# FullTouchSmartphone.net
KiCad netlist of a schematic drawn in EAGLE
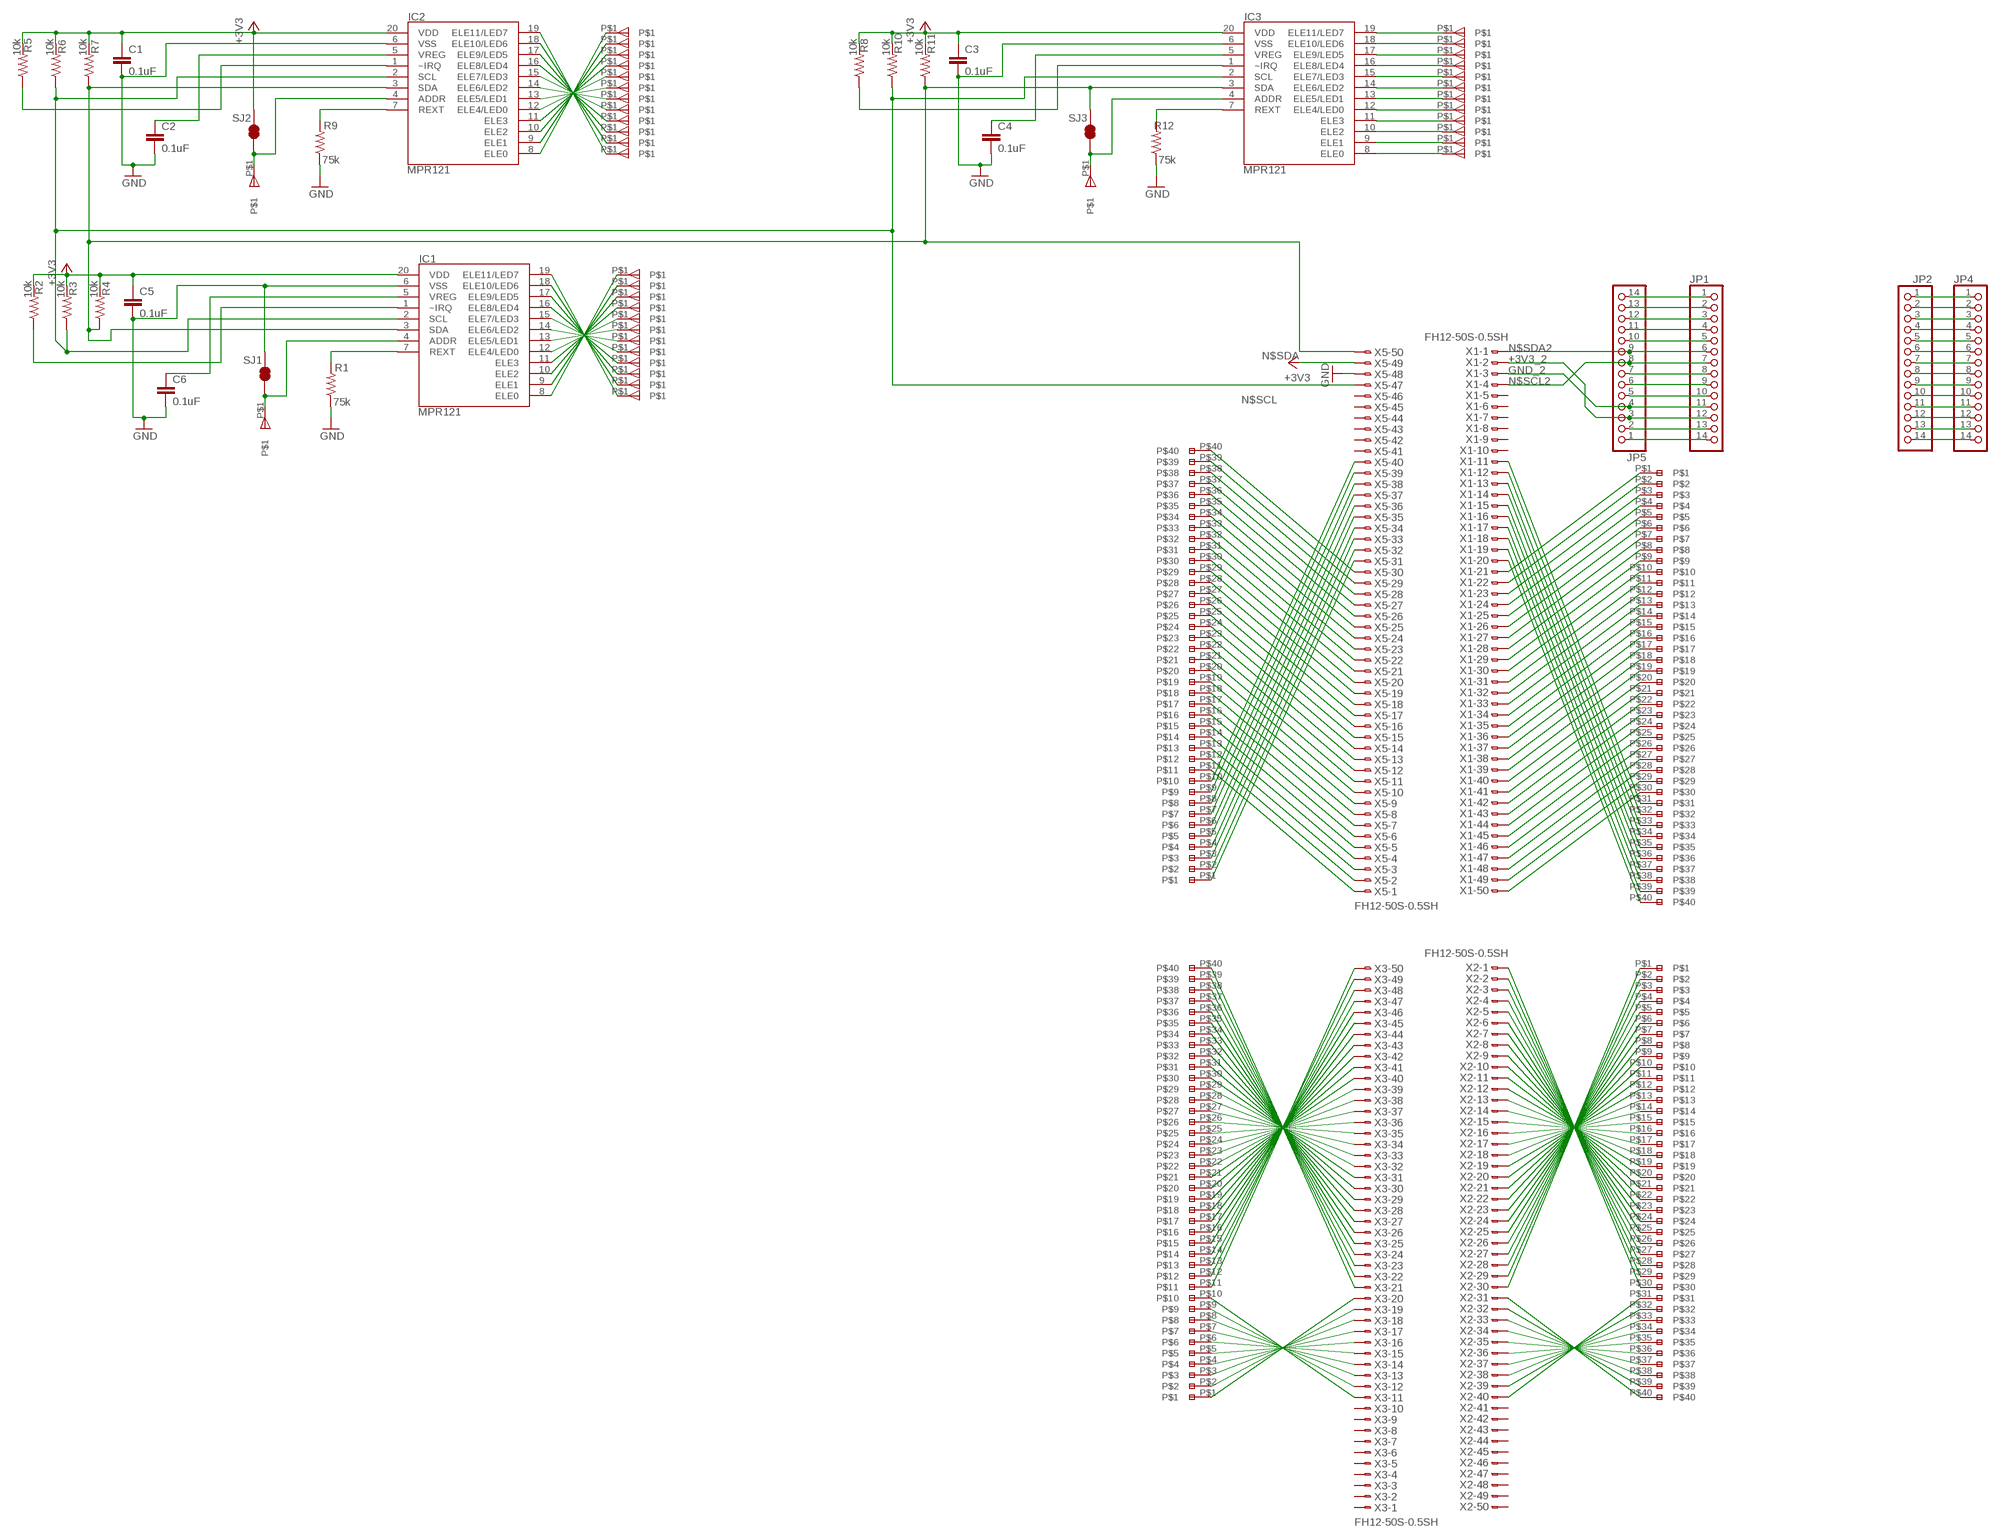
[diagram p0: schematic, sheet 1]

(export (version "E")
  (design (tool "Eeschema 10.0.6"))
  (components
    (comp (ref "C1")
      (value "0.1uF")
      (footprint "eagle-import:0603-CAP")
      (libsource (lib "eagle-import") (part "CAP0603-CAP"))
    )
    (comp (ref "C2")
      (value "0.1uF")
      (footprint "eagle-import:0603-CAP")
      (libsource (lib "eagle-import") (part "CAP0603-CAP"))
    )
    (comp (ref "C3")
      (value "0.1uF")
      (footprint "eagle-import:0603-CAP")
      (libsource (lib "eagle-import") (part "CAP0603-CAP"))
    )
    (comp (ref "C4")
      (value "0.1uF")
      (footprint "eagle-import:0603-CAP")
      (libsource (lib "eagle-import") (part "CAP0603-CAP"))
    )
    (comp (ref "C5")
      (value "0.1uF")
      (footprint "eagle-import:0603-CAP")
      (libsource (lib "eagle-import") (part "CAP0603-CAP"))
    )
    (comp (ref "C6")
      (value "0.1uF")
      (footprint "eagle-import:0603-CAP")
      (libsource (lib "eagle-import") (part "CAP0603-CAP"))
    )
    (comp (ref "IC1")
      (value "MPR121")
      (footprint "eagle-import:QFN-20-0.4MM-V2")
      (libsource (lib "eagle-import") (part "MPR121V2"))
    )
    (comp (ref "IC2")
      (value "MPR121")
      (footprint "eagle-import:QFN-20-0.4MM-V2")
      (libsource (lib "eagle-import") (part "MPR121V2"))
    )
    (comp (ref "IC3")
      (value "MPR121")
      (footprint "eagle-import:QFN-20-0.4MM-V2")
      (libsource (lib "eagle-import") (part "MPR121V2"))
    )
    (comp (ref "JP1")
      (value "PINHD-1X14")
      (footprint "eagle-import:1X14")
      (libsource (lib "eagle-import") (part "PINHD-1X14"))
    )
    (comp (ref "JP2")
      (value "PINHD-1X14")
      (footprint "eagle-import:1X14")
      (libsource (lib "eagle-import") (part "PINHD-1X14"))
    )
    (comp (ref "JP4")
      (value "PINHD-1X14")
      (footprint "eagle-import:1X14")
      (libsource (lib "eagle-import") (part "PINHD-1X14"))
    )
    (comp (ref "JP5")
      (value "PINHD-1X14")
      (footprint "eagle-import:1X14")
      (libsource (lib "eagle-import") (part "PINHD-1X14"))
    )
    (comp (ref "R1")
      (value "75k")
      (footprint "eagle-import:0603-RES")
      (libsource (lib "eagle-import") (part "RESISTOR0603-RES"))
    )
    (comp (ref "R2")
      (value "10k")
      (footprint "eagle-import:0603-RES")
      (libsource (lib "eagle-import") (part "RESISTOR0603-RES"))
    )
    (comp (ref "R3")
      (value "10k")
      (footprint "eagle-import:0603-RES")
      (libsource (lib "eagle-import") (part "RESISTOR0603-RES"))
    )
    (comp (ref "R4")
      (value "10k")
      (footprint "eagle-import:0603-RES")
      (libsource (lib "eagle-import") (part "RESISTOR0603-RES"))
    )
    (comp (ref "R5")
      (value "10k")
      (footprint "eagle-import:0603-RES")
      (libsource (lib "eagle-import") (part "RESISTOR0603-RES"))
    )
    (comp (ref "R6")
      (value "10k")
      (footprint "eagle-import:0603-RES")
      (libsource (lib "eagle-import") (part "RESISTOR0603-RES"))
    )
    (comp (ref "R7")
      (value "10k")
      (footprint "eagle-import:0603-RES")
      (libsource (lib "eagle-import") (part "RESISTOR0603-RES"))
    )
    (comp (ref "R8")
      (value "10k")
      (footprint "eagle-import:0603-RES")
      (libsource (lib "eagle-import") (part "RESISTOR0603-RES"))
    )
    (comp (ref "R9")
      (value "75k")
      (footprint "eagle-import:0603-RES")
      (libsource (lib "eagle-import") (part "RESISTOR0603-RES"))
    )
    (comp (ref "R10")
      (value "10k")
      (footprint "eagle-import:0603-RES")
      (libsource (lib "eagle-import") (part "RESISTOR0603-RES"))
    )
    (comp (ref "R11")
      (value "10k")
      (footprint "eagle-import:0603-RES")
      (libsource (lib "eagle-import") (part "RESISTOR0603-RES"))
    )
    (comp (ref "R12")
      (value "75k")
      (footprint "eagle-import:0603-RES")
      (libsource (lib "eagle-import") (part "RESISTOR0603-RES"))
    )
    (comp (ref "SJ1")
      (value "SOLDERJUMPERTRACE")
      (footprint "eagle-import:SJ_2S-TRACE")
      (libsource (lib "eagle-import") (part "SOLDERJUMPERTRACE"))
    )
    (comp (ref "SJ2")
      (value "SOLDERJUMPERTRACE")
      (footprint "eagle-import:SJ_2S-TRACE")
      (libsource (lib "eagle-import") (part "SOLDERJUMPERTRACE"))
    )
    (comp (ref "SJ3")
      (value "SOLDERJUMPERTRACE")
      (footprint "eagle-import:SJ_2S-TRACE")
      (libsource (lib "eagle-import") (part "SOLDERJUMPERTRACE"))
    )
    (comp (ref "U$1")
      (value "AXE640124")
      (footprint "eagle-import:AXE640124")
      (libsource (lib "eagle-import") (part "AXE640124"))
    )
    (comp (ref "U$2")
      (value "AXE640124")
      (footprint "eagle-import:AXE640124")
      (libsource (lib "eagle-import") (part "AXE640124"))
    )
    (comp (ref "U$3")
      (value "AXE540127")
      (footprint "eagle-import:AXE540127")
      (libsource (lib "eagle-import") (part "AXE540127"))
    )
    (comp (ref "U$4")
      (value "SINGLE_LÖT_SPOT_K")
      (footprint "eagle-import:SINGLE_LÖT_SPOT_K")
      (libsource (lib "eagle-import") (part "SINGLE_LÖT_SPOT_K"))
    )
    (comp (ref "U$5")
      (value "SINGLE_LÖT_SPOT_K")
      (footprint "eagle-import:SINGLE_LÖT_SPOT_K")
      (libsource (lib "eagle-import") (part "SINGLE_LÖT_SPOT_K"))
    )
    (comp (ref "U$6")
      (value "SINGLE_LÖT_SPOT_K")
      (footprint "eagle-import:SINGLE_LÖT_SPOT_K")
      (libsource (lib "eagle-import") (part "SINGLE_LÖT_SPOT_K"))
    )
    (comp (ref "U$7")
      (value "SINGLE_LÖT_SPOT_K")
      (footprint "eagle-import:SINGLE_LÖT_SPOT_K")
      (libsource (lib "eagle-import") (part "SINGLE_LÖT_SPOT_K"))
    )
    (comp (ref "U$8")
      (value "SINGLE_LÖT_SPOT_K")
      (footprint "eagle-import:SINGLE_LÖT_SPOT_K")
      (libsource (lib "eagle-import") (part "SINGLE_LÖT_SPOT_K"))
    )
    (comp (ref "U$9")
      (value "SINGLE_LÖT_SPOT_K")
      (footprint "eagle-import:SINGLE_LÖT_SPOT_K")
      (libsource (lib "eagle-import") (part "SINGLE_LÖT_SPOT_K"))
    )
    (comp (ref "U$10")
      (value "SINGLE_LÖT_SPOT_K")
      (footprint "eagle-import:SINGLE_LÖT_SPOT_K")
      (libsource (lib "eagle-import") (part "SINGLE_LÖT_SPOT_K"))
    )
    (comp (ref "U$11")
      (value "SINGLE_LÖT_SPOT_K")
      (footprint "eagle-import:SINGLE_LÖT_SPOT_K")
      (libsource (lib "eagle-import") (part "SINGLE_LÖT_SPOT_K"))
    )
    (comp (ref "U$12")
      (value "SINGLE_LÖT_SPOT_K")
      (footprint "eagle-import:SINGLE_LÖT_SPOT_K")
      (libsource (lib "eagle-import") (part "SINGLE_LÖT_SPOT_K"))
    )
    (comp (ref "U$13")
      (value "SINGLE_LÖT_SPOT_K")
      (footprint "eagle-import:SINGLE_LÖT_SPOT_K")
      (libsource (lib "eagle-import") (part "SINGLE_LÖT_SPOT_K"))
    )
    (comp (ref "U$14")
      (value "SINGLE_LÖT_SPOT_K")
      (footprint "eagle-import:SINGLE_LÖT_SPOT_K")
      (libsource (lib "eagle-import") (part "SINGLE_LÖT_SPOT_K"))
    )
    (comp (ref "U$15")
      (value "SINGLE_LÖT_SPOT_K")
      (footprint "eagle-import:SINGLE_LÖT_SPOT_K")
      (libsource (lib "eagle-import") (part "SINGLE_LÖT_SPOT_K"))
    )
    (comp (ref "U$25")
      (value "SINGLE_LÖT_SPOT_K")
      (footprint "eagle-import:SINGLE_LÖT_SPOT_K")
      (libsource (lib "eagle-import") (part "SINGLE_LÖT_SPOT_K"))
    )
    (comp (ref "U$26")
      (value "SINGLE_LÖT_SPOT_K")
      (footprint "eagle-import:SINGLE_LÖT_SPOT_K")
      (libsource (lib "eagle-import") (part "SINGLE_LÖT_SPOT_K"))
    )
    (comp (ref "U$27")
      (value "SINGLE_LÖT_SPOT_K")
      (footprint "eagle-import:SINGLE_LÖT_SPOT_K")
      (libsource (lib "eagle-import") (part "SINGLE_LÖT_SPOT_K"))
    )
    (comp (ref "U$28")
      (value "SINGLE_LÖT_SPOT_K")
      (footprint "eagle-import:SINGLE_LÖT_SPOT_K")
      (libsource (lib "eagle-import") (part "SINGLE_LÖT_SPOT_K"))
    )
    (comp (ref "U$29")
      (value "SINGLE_LÖT_SPOT_K")
      (footprint "eagle-import:SINGLE_LÖT_SPOT_K")
      (libsource (lib "eagle-import") (part "SINGLE_LÖT_SPOT_K"))
    )
    (comp (ref "U$30")
      (value "SINGLE_LÖT_SPOT_K")
      (footprint "eagle-import:SINGLE_LÖT_SPOT_K")
      (libsource (lib "eagle-import") (part "SINGLE_LÖT_SPOT_K"))
    )
    (comp (ref "U$31")
      (value "SINGLE_LÖT_SPOT_K")
      (footprint "eagle-import:SINGLE_LÖT_SPOT_K")
      (libsource (lib "eagle-import") (part "SINGLE_LÖT_SPOT_K"))
    )
    (comp (ref "U$32")
      (value "SINGLE_LÖT_SPOT_K")
      (footprint "eagle-import:SINGLE_LÖT_SPOT_K")
      (libsource (lib "eagle-import") (part "SINGLE_LÖT_SPOT_K"))
    )
    (comp (ref "U$33")
      (value "SINGLE_LÖT_SPOT_K")
      (footprint "eagle-import:SINGLE_LÖT_SPOT_K")
      (libsource (lib "eagle-import") (part "SINGLE_LÖT_SPOT_K"))
    )
    (comp (ref "U$34")
      (value "SINGLE_LÖT_SPOT_K")
      (footprint "eagle-import:SINGLE_LÖT_SPOT_K")
      (libsource (lib "eagle-import") (part "SINGLE_LÖT_SPOT_K"))
    )
    (comp (ref "U$35")
      (value "SINGLE_LÖT_SPOT_K")
      (footprint "eagle-import:SINGLE_LÖT_SPOT_K")
      (libsource (lib "eagle-import") (part "SINGLE_LÖT_SPOT_K"))
    )
    (comp (ref "U$36")
      (value "SINGLE_LÖT_SPOT_K")
      (footprint "eagle-import:SINGLE_LÖT_SPOT_K")
      (libsource (lib "eagle-import") (part "SINGLE_LÖT_SPOT_K"))
    )
    (comp (ref "U$37")
      (value "SINGLE_LÖT_SPOT_K")
      (footprint "eagle-import:SINGLE_LÖT_SPOT_K")
      (libsource (lib "eagle-import") (part "SINGLE_LÖT_SPOT_K"))
    )
    (comp (ref "U$38")
      (value "SINGLE_LÖT_SPOT_K")
      (footprint "eagle-import:SINGLE_LÖT_SPOT_K")
      (libsource (lib "eagle-import") (part "SINGLE_LÖT_SPOT_K"))
    )
    (comp (ref "U$39")
      (value "SINGLE_LÖT_SPOT_K")
      (footprint "eagle-import:SINGLE_LÖT_SPOT_K")
      (libsource (lib "eagle-import") (part "SINGLE_LÖT_SPOT_K"))
    )
    (comp (ref "U$40")
      (value "SINGLE_LÖT_SPOT_K")
      (footprint "eagle-import:SINGLE_LÖT_SPOT_K")
      (libsource (lib "eagle-import") (part "SINGLE_LÖT_SPOT_K"))
    )
    (comp (ref "U$40PIN-BACK")
      (value "AXE540127")
      (footprint "eagle-import:AXE540127")
      (libsource (lib "eagle-import") (part "AXE540127"))
    )
    (comp (ref "U$41")
      (value "SINGLE_LÖT_SPOT_K")
      (footprint "eagle-import:SINGLE_LÖT_SPOT_K")
      (libsource (lib "eagle-import") (part "SINGLE_LÖT_SPOT_K"))
    )
    (comp (ref "U$42")
      (value "SINGLE_LÖT_SPOT_K")
      (footprint "eagle-import:SINGLE_LÖT_SPOT_K")
      (libsource (lib "eagle-import") (part "SINGLE_LÖT_SPOT_K"))
    )
    (comp (ref "U$43")
      (value "SINGLE_LÖT_SPOT_K")
      (footprint "eagle-import:SINGLE_LÖT_SPOT_K")
      (libsource (lib "eagle-import") (part "SINGLE_LÖT_SPOT_K"))
    )
    (comp (ref "U$44")
      (value "SINGLE_LÖT_SPOT_K")
      (footprint "eagle-import:SINGLE_LÖT_SPOT_K")
      (libsource (lib "eagle-import") (part "SINGLE_LÖT_SPOT_K"))
    )
    (comp (ref "U$45")
      (value "SINGLE_LÖT_SPOT_K")
      (footprint "eagle-import:SINGLE_LÖT_SPOT_K")
      (libsource (lib "eagle-import") (part "SINGLE_LÖT_SPOT_K"))
    )
    (comp (ref "U$46")
      (value "SINGLE_LÖT_SPOT_K")
      (footprint "eagle-import:SINGLE_LÖT_SPOT_K")
      (libsource (lib "eagle-import") (part "SINGLE_LÖT_SPOT_K"))
    )
    (comp (ref "U$47")
      (value "SINGLE_LÖT_SPOT_K")
      (footprint "eagle-import:SINGLE_LÖT_SPOT_K")
      (libsource (lib "eagle-import") (part "SINGLE_LÖT_SPOT_K"))
    )
    (comp (ref "U$48")
      (value "SINGLE_LÖT_SPOT_K")
      (footprint "eagle-import:SINGLE_LÖT_SPOT_K")
      (libsource (lib "eagle-import") (part "SINGLE_LÖT_SPOT_K"))
    )
    (comp (ref "U$49")
      (value "SINGLE_LÖT_SPOT_K")
      (footprint "eagle-import:SINGLE_LÖT_SPOT_K")
      (libsource (lib "eagle-import") (part "SINGLE_LÖT_SPOT_K"))
    )
    (comp (ref "U$50")
      (value "SINGLE_LÖT_SPOT_K")
      (footprint "eagle-import:SINGLE_LÖT_SPOT_K")
      (libsource (lib "eagle-import") (part "SINGLE_LÖT_SPOT_K"))
    )
    (comp (ref "U$51")
      (value "SINGLE_LÖT_SPOT_K")
      (footprint "eagle-import:SINGLE_LÖT_SPOT_K")
      (libsource (lib "eagle-import") (part "SINGLE_LÖT_SPOT_K"))
    )
    (comp (ref "X1")
      (value "FH12-50S-0.5SH")
      (footprint "eagle-import:FH12-50S-0.5SH")
      (fields (field (name "MPN") "FH12-50S-0.5SH(55)"))
      (libsource (lib "eagle-import") (part "FH12-50S-0.5SH"))
    )
    (comp (ref "X2")
      (value "FH12-50S-0.5SH")
      (footprint "eagle-import:FH12-50S-0.5SH")
      (fields (field (name "MPN") "FH12-50S-0.5SH(55)"))
      (libsource (lib "eagle-import") (part "FH12-50S-0.5SH"))
    )
    (comp (ref "X3")
      (value "FH12-50S-0.5SH")
      (footprint "eagle-import:FH12-50S-0.5SH")
      (fields (field (name "MPN") "FH12-50S-0.5SH(55)"))
      (libsource (lib "eagle-import") (part "FH12-50S-0.5SH"))
    )
    (comp (ref "X5")
      (value "FH12-50S-0.5SH")
      (footprint "eagle-import:FH12-50S-0.5SH")
      (fields (field (name "MPN") "FH12-50S-0.5SH(55)"))
      (libsource (lib "eagle-import") (part "FH12-50S-0.5SH"))
    )
  )
  (nets
    (net (code "1") (name "+3V3") (class "Default")
      (node (ref "C1") (pin "1") (pinfunction "1_1") (pintype "passive"))
      (node (ref "C3") (pin "1") (pinfunction "1_1") (pintype "passive"))
      (node (ref "C5") (pin "1") (pinfunction "1_1") (pintype "passive"))
      (node (ref "IC1") (pin "20") (pinfunction "VDD_20") (pintype "bidirectional"))
      (node (ref "IC2") (pin "20") (pinfunction "VDD_20") (pintype "bidirectional"))
      (node (ref "IC3") (pin "20") (pinfunction "VDD_20") (pintype "bidirectional"))
      (node (ref "R10") (pin "2") (pinfunction "2_2") (pintype "passive"))
      (node (ref "R11") (pin "2") (pinfunction "2_2") (pintype "passive"))
      (node (ref "R2") (pin "2") (pinfunction "2_2") (pintype "passive"))
      (node (ref "R3") (pin "2") (pinfunction "2_2") (pintype "passive"))
      (node (ref "R4") (pin "2") (pinfunction "2_2") (pintype "passive"))
      (node (ref "R5") (pin "2") (pinfunction "2_2") (pintype "passive"))
      (node (ref "R6") (pin "2") (pinfunction "2_2") (pintype "passive"))
      (node (ref "R7") (pin "2") (pinfunction "2_2") (pintype "passive"))
      (node (ref "R8") (pin "2") (pinfunction "2_2") (pintype "passive"))
      (node (ref "SJ2") (pin "2") (pinfunction "2_2") (pintype "passive"))
      (node (ref "X5") (pin "49") (pinfunction "1_49") (pintype "passive"))
    )
    (net (code "2") (name "/+3V3_2") (class "Default")
      (node (ref "JP1") (pin "12") (pinfunction "12_12") (pintype "passive"))
      (node (ref "JP5") (pin "3") (pinfunction "3_3") (pintype "passive"))
      (node (ref "X1") (pin "2") (pinfunction "1_2") (pintype "passive"))
    )
    (net (code "3") (name "/GND_2") (class "Default")
      (node (ref "JP1") (pin "11") (pinfunction "11_11") (pintype "passive"))
      (node (ref "JP5") (pin "4") (pinfunction "4_4") (pintype "passive"))
      (node (ref "X1") (pin "3") (pinfunction "1_3") (pintype "passive"))
    )
    (net (code "4") (name "/N$SCL") (class "Default")
      (node (ref "IC1") (pin "2") (pinfunction "SCL_2") (pintype "bidirectional"))
      (node (ref "IC2") (pin "2") (pinfunction "SCL_2") (pintype "bidirectional"))
      (node (ref "IC3") (pin "2") (pinfunction "SCL_2") (pintype "bidirectional"))
      (node (ref "R10") (pin "1") (pinfunction "1_1") (pintype "passive"))
      (node (ref "R3") (pin "1") (pinfunction "1_1") (pintype "passive"))
      (node (ref "R6") (pin "1") (pinfunction "1_1") (pintype "passive"))
      (node (ref "X5") (pin "47") (pinfunction "1_47") (pintype "passive"))
    )
    (net (code "5") (name "/N$SCL2") (class "Default")
      (node (ref "JP1") (pin "7") (pinfunction "7_7") (pintype "passive"))
      (node (ref "JP5") (pin "8") (pinfunction "8_8") (pintype "passive"))
      (node (ref "X1") (pin "4") (pinfunction "1_4") (pintype "passive"))
    )
    (net (code "6") (name "/N$SDA") (class "Default")
      (node (ref "IC1") (pin "3") (pinfunction "SDA_3") (pintype "bidirectional"))
      (node (ref "IC2") (pin "3") (pinfunction "SDA_3") (pintype "bidirectional"))
      (node (ref "IC3") (pin "3") (pinfunction "SDA_3") (pintype "bidirectional"))
      (node (ref "R11") (pin "1") (pinfunction "1_1") (pintype "passive"))
      (node (ref "R4") (pin "1") (pinfunction "1_1") (pintype "passive"))
      (node (ref "R7") (pin "1") (pinfunction "1_1") (pintype "passive"))
      (node (ref "SJ3") (pin "2") (pinfunction "2_2") (pintype "passive"))
      (node (ref "X5") (pin "50") (pinfunction "1_50") (pintype "passive"))
    )
    (net (code "7") (name "/N$SDA2") (class "Default")
      (node (ref "JP1") (pin "6") (pinfunction "6_6") (pintype "passive"))
      (node (ref "JP5") (pin "9") (pinfunction "9_9") (pintype "passive"))
      (node (ref "X1") (pin "1") (pinfunction "1_1") (pintype "passive"))
    )
    (net (code "8") (name "GND") (class "Default")
      (node (ref "C1") (pin "2") (pinfunction "2_2") (pintype "passive"))
      (node (ref "C2") (pin "2") (pinfunction "2_2") (pintype "passive"))
      (node (ref "C3") (pin "2") (pinfunction "2_2") (pintype "passive"))
      (node (ref "C4") (pin "2") (pinfunction "2_2") (pintype "passive"))
      (node (ref "C5") (pin "2") (pinfunction "2_2") (pintype "passive"))
      (node (ref "C6") (pin "2") (pinfunction "2_2") (pintype "passive"))
      (node (ref "IC1") (pin "6") (pinfunction "VSS_6") (pintype "bidirectional"))
      (node (ref "IC2") (pin "6") (pinfunction "VSS_6") (pintype "bidirectional"))
      (node (ref "IC3") (pin "6") (pinfunction "VSS_6") (pintype "bidirectional"))
      (node (ref "R1") (pin "1") (pinfunction "1_1") (pintype "passive"))
      (node (ref "R12") (pin "1") (pinfunction "1_1") (pintype "passive"))
      (node (ref "R9") (pin "1") (pinfunction "1_1") (pintype "passive"))
      (node (ref "SJ1") (pin "2") (pinfunction "2_2") (pintype "passive"))
      (node (ref "X5") (pin "48") (pinfunction "1_48") (pintype "passive"))
    )
    (net (code "9") (name "Net-(IC1-ADDR)") (class "Default")
      (node (ref "IC1") (pin "4") (pinfunction "ADDR_4") (pintype "bidirectional"))
      (node (ref "SJ1") (pin "1") (pinfunction "1_1") (pintype "passive"))
      (node (ref "U$37") (pin "P$1") (pinfunction "P$1_P$1") (pintype "passive"))
    )
    (net (code "10") (name "Net-(IC1-ELE0)") (class "Default")
      (node (ref "IC1") (pin "8") (pinfunction "ELE0_8") (pintype "bidirectional"))
      (node (ref "U$4") (pin "P$1") (pinfunction "P$1_P$1") (pintype "passive"))
    )
    (net (code "11") (name "Net-(IC1-ELE1)") (class "Default")
      (node (ref "IC1") (pin "9") (pinfunction "ELE1_9") (pintype "bidirectional"))
      (node (ref "U$5") (pin "P$1") (pinfunction "P$1_P$1") (pintype "passive"))
    )
    (net (code "12") (name "Net-(IC1-ELE2)") (class "Default")
      (node (ref "IC1") (pin "10") (pinfunction "ELE2_10") (pintype "bidirectional"))
      (node (ref "U$6") (pin "P$1") (pinfunction "P$1_P$1") (pintype "passive"))
    )
    (net (code "13") (name "Net-(IC1-ELE3)") (class "Default")
      (node (ref "IC1") (pin "11") (pinfunction "ELE3_11") (pintype "bidirectional"))
      (node (ref "U$7") (pin "P$1") (pinfunction "P$1_P$1") (pintype "passive"))
    )
    (net (code "14") (name "Net-(IC1-ELE4{slash}LED0)") (class "Default")
      (node (ref "IC1") (pin "12") (pinfunction "ELE4/LED0_12") (pintype "bidirectional"))
      (node (ref "U$8") (pin "P$1") (pinfunction "P$1_P$1") (pintype "passive"))
    )
    (net (code "15") (name "Net-(IC1-ELE5{slash}LED1)") (class "Default")
      (node (ref "IC1") (pin "13") (pinfunction "ELE5/LED1_13") (pintype "bidirectional"))
      (node (ref "U$9") (pin "P$1") (pinfunction "P$1_P$1") (pintype "passive"))
    )
    (net (code "16") (name "Net-(IC1-ELE6{slash}LED2)") (class "Default")
      (node (ref "IC1") (pin "14") (pinfunction "ELE6/LED2_14") (pintype "bidirectional"))
      (node (ref "U$10") (pin "P$1") (pinfunction "P$1_P$1") (pintype "passive"))
    )
    (net (code "17") (name "Net-(IC1-ELE7{slash}LED3)") (class "Default")
      (node (ref "IC1") (pin "15") (pinfunction "ELE7/LED3_15") (pintype "bidirectional"))
      (node (ref "U$11") (pin "P$1") (pinfunction "P$1_P$1") (pintype "passive"))
    )
    (net (code "18") (name "Net-(IC1-ELE8{slash}LED4)") (class "Default")
      (node (ref "IC1") (pin "16") (pinfunction "ELE8/LED4_16") (pintype "bidirectional"))
      (node (ref "U$12") (pin "P$1") (pinfunction "P$1_P$1") (pintype "passive"))
    )
    (net (code "19") (name "Net-(IC1-ELE9{slash}LED5)") (class "Default")
      (node (ref "IC1") (pin "17") (pinfunction "ELE9/LED5_17") (pintype "bidirectional"))
      (node (ref "U$13") (pin "P$1") (pinfunction "P$1_P$1") (pintype "passive"))
    )
    (net (code "20") (name "Net-(IC1-ELE10{slash}LED6)") (class "Default")
      (node (ref "IC1") (pin "18") (pinfunction "ELE10/LED6_18") (pintype "bidirectional"))
      (node (ref "U$14") (pin "P$1") (pinfunction "P$1_P$1") (pintype "passive"))
    )
    (net (code "21") (name "Net-(IC1-ELE11{slash}LED7)") (class "Default")
      (node (ref "IC1") (pin "19") (pinfunction "ELE11/LED7_19") (pintype "bidirectional"))
      (node (ref "U$15") (pin "P$1") (pinfunction "P$1_P$1") (pintype "passive"))
    )
    (net (code "22") (name "Net-(IC1-REXT)") (class "Default")
      (node (ref "IC1") (pin "7") (pinfunction "REXT_7") (pintype "bidirectional"))
      (node (ref "R1") (pin "2") (pinfunction "2_2") (pintype "passive"))
    )
    (net (code "23") (name "Net-(IC1-VREG)") (class "Default")
      (node (ref "C6") (pin "1") (pinfunction "1_1") (pintype "passive"))
      (node (ref "IC1") (pin "5") (pinfunction "VREG_5") (pintype "bidirectional"))
    )
    (net (code "24") (name "Net-(IC1-~{IRQ})") (class "Default")
      (node (ref "IC1") (pin "1") (pinfunction "~{IRQ}_1") (pintype "bidirectional"))
      (node (ref "R2") (pin "1") (pinfunction "1_1") (pintype "passive"))
    )
    (net (code "25") (name "Net-(IC2-ADDR)") (class "Default")
      (node (ref "IC2") (pin "4") (pinfunction "ADDR_4") (pintype "bidirectional"))
      (node (ref "SJ2") (pin "1") (pinfunction "1_1") (pintype "passive"))
      (node (ref "U$38") (pin "P$1") (pinfunction "P$1_P$1") (pintype "passive"))
    )
    (net (code "26") (name "Net-(IC2-ELE0)") (class "Default")
      (node (ref "IC2") (pin "8") (pinfunction "ELE0_8") (pintype "bidirectional"))
      (node (ref "U$36") (pin "P$1") (pinfunction "P$1_P$1") (pintype "passive"))
    )
    (net (code "27") (name "Net-(IC2-ELE1)") (class "Default")
      (node (ref "IC2") (pin "9") (pinfunction "ELE1_9") (pintype "bidirectional"))
      (node (ref "U$35") (pin "P$1") (pinfunction "P$1_P$1") (pintype "passive"))
    )
    (net (code "28") (name "Net-(IC2-ELE2)") (class "Default")
      (node (ref "IC2") (pin "10") (pinfunction "ELE2_10") (pintype "bidirectional"))
      (node (ref "U$34") (pin "P$1") (pinfunction "P$1_P$1") (pintype "passive"))
    )
    (net (code "29") (name "Net-(IC2-ELE3)") (class "Default")
      (node (ref "IC2") (pin "11") (pinfunction "ELE3_11") (pintype "bidirectional"))
      (node (ref "U$33") (pin "P$1") (pinfunction "P$1_P$1") (pintype "passive"))
    )
    (net (code "30") (name "Net-(IC2-ELE4{slash}LED0)") (class "Default")
      (node (ref "IC2") (pin "12") (pinfunction "ELE4/LED0_12") (pintype "bidirectional"))
      (node (ref "U$32") (pin "P$1") (pinfunction "P$1_P$1") (pintype "passive"))
    )
    (net (code "31") (name "Net-(IC2-ELE5{slash}LED1)") (class "Default")
      (node (ref "IC2") (pin "13") (pinfunction "ELE5/LED1_13") (pintype "bidirectional"))
      (node (ref "U$31") (pin "P$1") (pinfunction "P$1_P$1") (pintype "passive"))
    )
    (net (code "32") (name "Net-(IC2-ELE6{slash}LED2)") (class "Default")
      (node (ref "IC2") (pin "14") (pinfunction "ELE6/LED2_14") (pintype "bidirectional"))
      (node (ref "U$30") (pin "P$1") (pinfunction "P$1_P$1") (pintype "passive"))
    )
    (net (code "33") (name "Net-(IC2-ELE7{slash}LED3)") (class "Default")
      (node (ref "IC2") (pin "15") (pinfunction "ELE7/LED3_15") (pintype "bidirectional"))
      (node (ref "U$29") (pin "P$1") (pinfunction "P$1_P$1") (pintype "passive"))
    )
    (net (code "34") (name "Net-(IC2-ELE8{slash}LED4)") (class "Default")
      (node (ref "IC2") (pin "16") (pinfunction "ELE8/LED4_16") (pintype "bidirectional"))
      (node (ref "U$28") (pin "P$1") (pinfunction "P$1_P$1") (pintype "passive"))
    )
    (net (code "35") (name "Net-(IC2-ELE9{slash}LED5)") (class "Default")
      (node (ref "IC2") (pin "17") (pinfunction "ELE9/LED5_17") (pintype "bidirectional"))
      (node (ref "U$27") (pin "P$1") (pinfunction "P$1_P$1") (pintype "passive"))
    )
    (net (code "36") (name "Net-(IC2-ELE10{slash}LED6)") (class "Default")
      (node (ref "IC2") (pin "18") (pinfunction "ELE10/LED6_18") (pintype "bidirectional"))
      (node (ref "U$26") (pin "P$1") (pinfunction "P$1_P$1") (pintype "passive"))
    )
    (net (code "37") (name "Net-(IC2-ELE11{slash}LED7)") (class "Default")
      (node (ref "IC2") (pin "19") (pinfunction "ELE11/LED7_19") (pintype "bidirectional"))
      (node (ref "U$25") (pin "P$1") (pinfunction "P$1_P$1") (pintype "passive"))
    )
    (net (code "38") (name "Net-(IC2-REXT)") (class "Default")
      (node (ref "IC2") (pin "7") (pinfunction "REXT_7") (pintype "bidirectional"))
      (node (ref "R9") (pin "2") (pinfunction "2_2") (pintype "passive"))
    )
    (net (code "39") (name "Net-(IC2-VREG)") (class "Default")
      (node (ref "C2") (pin "1") (pinfunction "1_1") (pintype "passive"))
      (node (ref "IC2") (pin "5") (pinfunction "VREG_5") (pintype "bidirectional"))
    )
    (net (code "40") (name "Net-(IC2-~{IRQ})") (class "Default")
      (node (ref "IC2") (pin "1") (pinfunction "~{IRQ}_1") (pintype "bidirectional"))
      (node (ref "R5") (pin "1") (pinfunction "1_1") (pintype "passive"))
    )
    (net (code "41") (name "Net-(IC3-ADDR)") (class "Default")
      (node (ref "IC3") (pin "4") (pinfunction "ADDR_4") (pintype "bidirectional"))
      (node (ref "SJ3") (pin "1") (pinfunction "1_1") (pintype "passive"))
      (node (ref "U$39") (pin "P$1") (pinfunction "P$1_P$1") (pintype "passive"))
    )
    (net (code "42") (name "Net-(IC3-ELE0)") (class "Default")
      (node (ref "IC3") (pin "8") (pinfunction "ELE0_8") (pintype "bidirectional"))
      (node (ref "U$51") (pin "P$1") (pinfunction "P$1_P$1") (pintype "passive"))
    )
    (net (code "43") (name "Net-(IC3-ELE1)") (class "Default")
      (node (ref "IC3") (pin "9") (pinfunction "ELE1_9") (pintype "bidirectional"))
      (node (ref "U$50") (pin "P$1") (pinfunction "P$1_P$1") (pintype "passive"))
    )
    (net (code "44") (name "Net-(IC3-ELE2)") (class "Default")
      (node (ref "IC3") (pin "10") (pinfunction "ELE2_10") (pintype "bidirectional"))
      (node (ref "U$49") (pin "P$1") (pinfunction "P$1_P$1") (pintype "passive"))
    )
    (net (code "45") (name "Net-(IC3-ELE3)") (class "Default")
      (node (ref "IC3") (pin "11") (pinfunction "ELE3_11") (pintype "bidirectional"))
      (node (ref "U$48") (pin "P$1") (pinfunction "P$1_P$1") (pintype "passive"))
    )
    (net (code "46") (name "Net-(IC3-ELE4{slash}LED0)") (class "Default")
      (node (ref "IC3") (pin "12") (pinfunction "ELE4/LED0_12") (pintype "bidirectional"))
      (node (ref "U$47") (pin "P$1") (pinfunction "P$1_P$1") (pintype "passive"))
    )
    (net (code "47") (name "Net-(IC3-ELE5{slash}LED1)") (class "Default")
      (node (ref "IC3") (pin "13") (pinfunction "ELE5/LED1_13") (pintype "bidirectional"))
      (node (ref "U$46") (pin "P$1") (pinfunction "P$1_P$1") (pintype "passive"))
    )
    (net (code "48") (name "Net-(IC3-ELE6{slash}LED2)") (class "Default")
      (node (ref "IC3") (pin "14") (pinfunction "ELE6/LED2_14") (pintype "bidirectional"))
      (node (ref "U$45") (pin "P$1") (pinfunction "P$1_P$1") (pintype "passive"))
    )
    (net (code "49") (name "Net-(IC3-ELE7{slash}LED3)") (class "Default")
      (node (ref "IC3") (pin "15") (pinfunction "ELE7/LED3_15") (pintype "bidirectional"))
      (node (ref "U$44") (pin "P$1") (pinfunction "P$1_P$1") (pintype "passive"))
    )
    (net (code "50") (name "Net-(IC3-ELE8{slash}LED4)") (class "Default")
      (node (ref "IC3") (pin "16") (pinfunction "ELE8/LED4_16") (pintype "bidirectional"))
      (node (ref "U$43") (pin "P$1") (pinfunction "P$1_P$1") (pintype "passive"))
    )
    (net (code "51") (name "Net-(IC3-ELE9{slash}LED5)") (class "Default")
      (node (ref "IC3") (pin "17") (pinfunction "ELE9/LED5_17") (pintype "bidirectional"))
      (node (ref "U$42") (pin "P$1") (pinfunction "P$1_P$1") (pintype "passive"))
    )
    (net (code "52") (name "Net-(IC3-ELE10{slash}LED6)") (class "Default")
      (node (ref "IC3") (pin "18") (pinfunction "ELE10/LED6_18") (pintype "bidirectional"))
      (node (ref "U$41") (pin "P$1") (pinfunction "P$1_P$1") (pintype "passive"))
    )
    (net (code "53") (name "Net-(IC3-ELE11{slash}LED7)") (class "Default")
      (node (ref "IC3") (pin "19") (pinfunction "ELE11/LED7_19") (pintype "bidirectional"))
      (node (ref "U$40") (pin "P$1") (pinfunction "P$1_P$1") (pintype "passive"))
    )
    (net (code "54") (name "Net-(IC3-REXT)") (class "Default")
      (node (ref "IC3") (pin "7") (pinfunction "REXT_7") (pintype "bidirectional"))
      (node (ref "R12") (pin "2") (pinfunction "2_2") (pintype "passive"))
    )
    (net (code "55") (name "Net-(IC3-VREG)") (class "Default")
      (node (ref "C4") (pin "1") (pinfunction "1_1") (pintype "passive"))
      (node (ref "IC3") (pin "5") (pinfunction "VREG_5") (pintype "bidirectional"))
    )
    (net (code "56") (name "Net-(IC3-~{IRQ})") (class "Default")
      (node (ref "IC3") (pin "1") (pinfunction "~{IRQ}_1") (pintype "bidirectional"))
      (node (ref "R8") (pin "1") (pinfunction "1_1") (pintype "passive"))
    )
    (net (code "57") (name "Net-(JP1-Pad1)") (class "Default")
      (node (ref "JP1") (pin "1") (pinfunction "1_1") (pintype "passive"))
      (node (ref "JP5") (pin "14") (pinfunction "14_14") (pintype "passive"))
    )
    (net (code "58") (name "Net-(JP1-Pad2)") (class "Default")
      (node (ref "JP1") (pin "2") (pinfunction "2_2") (pintype "passive"))
      (node (ref "JP5") (pin "13") (pinfunction "13_13") (pintype "passive"))
    )
    (net (code "59") (name "Net-(JP1-Pad3)") (class "Default")
      (node (ref "JP1") (pin "3") (pinfunction "3_3") (pintype "passive"))
      (node (ref "JP5") (pin "12") (pinfunction "12_12") (pintype "passive"))
    )
    (net (code "60") (name "Net-(JP1-Pad4)") (class "Default")
      (node (ref "JP1") (pin "4") (pinfunction "4_4") (pintype "passive"))
      (node (ref "JP5") (pin "11") (pinfunction "11_11") (pintype "passive"))
    )
    (net (code "61") (name "Net-(JP1-Pad5)") (class "Default")
      (node (ref "JP1") (pin "5") (pinfunction "5_5") (pintype "passive"))
      (node (ref "JP5") (pin "10") (pinfunction "10_10") (pintype "passive"))
    )
    (net (code "62") (name "Net-(JP1-Pad8)") (class "Default")
      (node (ref "JP1") (pin "8") (pinfunction "8_8") (pintype "passive"))
      (node (ref "JP5") (pin "7") (pinfunction "7_7") (pintype "passive"))
    )
    (net (code "63") (name "Net-(JP1-Pad9)") (class "Default")
      (node (ref "JP1") (pin "9") (pinfunction "9_9") (pintype "passive"))
      (node (ref "JP5") (pin "6") (pinfunction "6_6") (pintype "passive"))
    )
    (net (code "64") (name "Net-(JP1-Pad10)") (class "Default")
      (node (ref "JP1") (pin "10") (pinfunction "10_10") (pintype "passive"))
      (node (ref "JP5") (pin "5") (pinfunction "5_5") (pintype "passive"))
    )
    (net (code "65") (name "Net-(JP1-Pad13)") (class "Default")
      (node (ref "JP1") (pin "13") (pinfunction "13_13") (pintype "passive"))
      (node (ref "JP5") (pin "2") (pinfunction "2_2") (pintype "passive"))
    )
    (net (code "66") (name "Net-(JP1-Pad14)") (class "Default")
      (node (ref "JP1") (pin "14") (pinfunction "14_14") (pintype "passive"))
      (node (ref "JP5") (pin "1") (pinfunction "1_1") (pintype "passive"))
    )
    (net (code "67") (name "Net-(JP2-Pad1)") (class "Default")
      (node (ref "JP2") (pin "1") (pinfunction "1_1") (pintype "passive"))
      (node (ref "JP4") (pin "1") (pinfunction "1_1") (pintype "passive"))
    )
    (net (code "68") (name "Net-(JP2-Pad2)") (class "Default")
      (node (ref "JP2") (pin "2") (pinfunction "2_2") (pintype "passive"))
      (node (ref "JP4") (pin "2") (pinfunction "2_2") (pintype "passive"))
    )
    (net (code "69") (name "Net-(JP2-Pad3)") (class "Default")
      (node (ref "JP2") (pin "3") (pinfunction "3_3") (pintype "passive"))
      (node (ref "JP4") (pin "3") (pinfunction "3_3") (pintype "passive"))
    )
    (net (code "70") (name "Net-(JP2-Pad4)") (class "Default")
      (node (ref "JP2") (pin "4") (pinfunction "4_4") (pintype "passive"))
      (node (ref "JP4") (pin "4") (pinfunction "4_4") (pintype "passive"))
    )
    (net (code "71") (name "Net-(JP2-Pad5)") (class "Default")
      (node (ref "JP2") (pin "5") (pinfunction "5_5") (pintype "passive"))
      (node (ref "JP4") (pin "5") (pinfunction "5_5") (pintype "passive"))
    )
    (net (code "72") (name "Net-(JP2-Pad6)") (class "Default")
      (node (ref "JP2") (pin "6") (pinfunction "6_6") (pintype "passive"))
      (node (ref "JP4") (pin "6") (pinfunction "6_6") (pintype "passive"))
    )
    (net (code "73") (name "Net-(JP2-Pad7)") (class "Default")
      (node (ref "JP2") (pin "7") (pinfunction "7_7") (pintype "passive"))
      (node (ref "JP4") (pin "7") (pinfunction "7_7") (pintype "passive"))
    )
    (net (code "74") (name "Net-(JP2-Pad8)") (class "Default")
      (node (ref "JP2") (pin "8") (pinfunction "8_8") (pintype "passive"))
      (node (ref "JP4") (pin "8") (pinfunction "8_8") (pintype "passive"))
    )
    (net (code "75") (name "Net-(JP2-Pad9)") (class "Default")
      (node (ref "JP2") (pin "9") (pinfunction "9_9") (pintype "passive"))
      (node (ref "JP4") (pin "9") (pinfunction "9_9") (pintype "passive"))
    )
    (net (code "76") (name "Net-(JP2-Pad10)") (class "Default")
      (node (ref "JP2") (pin "10") (pinfunction "10_10") (pintype "passive"))
      (node (ref "JP4") (pin "10") (pinfunction "10_10") (pintype "passive"))
    )
    (net (code "77") (name "Net-(JP2-Pad11)") (class "Default")
      (node (ref "JP2") (pin "11") (pinfunction "11_11") (pintype "passive"))
      (node (ref "JP4") (pin "11") (pinfunction "11_11") (pintype "passive"))
    )
    (net (code "78") (name "Net-(JP2-Pad12)") (class "Default")
      (node (ref "JP2") (pin "12") (pinfunction "12_12") (pintype "passive"))
      (node (ref "JP4") (pin "12") (pinfunction "12_12") (pintype "passive"))
    )
    (net (code "79") (name "Net-(JP2-Pad13)") (class "Default")
      (node (ref "JP2") (pin "13") (pinfunction "13_13") (pintype "passive"))
      (node (ref "JP4") (pin "13") (pinfunction "13_13") (pintype "passive"))
    )
    (net (code "80") (name "Net-(JP2-Pad14)") (class "Default")
      (node (ref "JP2") (pin "14") (pinfunction "14_14") (pintype "passive"))
      (node (ref "JP4") (pin "14") (pinfunction "14_14") (pintype "passive"))
    )
    (net (code "81") (name "Net-(U$1-PadP$30)") (class "Default")
      (node (ref "U$1") (pin "P$30") (pinfunction "P$30_P$30") (pintype "passive"))
      (node (ref "X2") (pin "1") (pinfunction "1_1") (pintype "passive"))
    )
    (net (code "82") (name "Net-(U$40PIN-BACK-PadP$11)") (class "Default")
      (node (ref "U$40PIN-BACK") (pin "P$11") (pinfunction "P$11_P$11") (pintype "passive"))
      (node (ref "X5") (pin "1") (pinfunction "1_1") (pintype "passive"))
    )
    (net (code "83") (name "Net-(X1AA-1)") (class "Default")
      (node (ref "U$2") (pin "P$13") (pinfunction "P$13_P$13") (pintype "passive"))
      (node (ref "X1") (pin "33") (pinfunction "1_33") (pintype "passive"))
    )
    (net (code "84") (name "Net-(X1AB-1)") (class "Default")
      (node (ref "U$2") (pin "P$14") (pinfunction "P$14_P$14") (pintype "passive"))
      (node (ref "X1") (pin "34") (pinfunction "1_34") (pintype "passive"))
    )
    (net (code "85") (name "Net-(X1AC-1)") (class "Default")
      (node (ref "U$2") (pin "P$15") (pinfunction "P$15_P$15") (pintype "passive"))
      (node (ref "X1") (pin "35") (pinfunction "1_35") (pintype "passive"))
    )
    (net (code "86") (name "Net-(X1AD-1)") (class "Default")
      (node (ref "U$2") (pin "P$16") (pinfunction "P$16_P$16") (pintype "passive"))
      (node (ref "X1") (pin "36") (pinfunction "1_36") (pintype "passive"))
    )
    (net (code "87") (name "Net-(X1AE-1)") (class "Default")
      (node (ref "U$2") (pin "P$17") (pinfunction "P$17_P$17") (pintype "passive"))
      (node (ref "X1") (pin "37") (pinfunction "1_37") (pintype "passive"))
    )
    (net (code "88") (name "Net-(X1AF-1)") (class "Default")
      (node (ref "U$2") (pin "P$18") (pinfunction "P$18_P$18") (pintype "passive"))
      (node (ref "X1") (pin "38") (pinfunction "1_38") (pintype "passive"))
    )
    (net (code "89") (name "Net-(X1AG-1)") (class "Default")
      (node (ref "U$2") (pin "P$19") (pinfunction "P$19_P$19") (pintype "passive"))
      (node (ref "X1") (pin "39") (pinfunction "1_39") (pintype "passive"))
    )
    (net (code "90") (name "Net-(X1AI-1)") (class "Default")
      (node (ref "U$2") (pin "P$20") (pinfunction "P$20_P$20") (pintype "passive"))
      (node (ref "X1") (pin "40") (pinfunction "1_40") (pintype "passive"))
    )
    (net (code "91") (name "Net-(X1AJ-1)") (class "Default")
      (node (ref "U$2") (pin "P$21") (pinfunction "P$21_P$21") (pintype "passive"))
      (node (ref "X1") (pin "41") (pinfunction "1_41") (pintype "passive"))
    )
    (net (code "92") (name "Net-(X1AK-1)") (class "Default")
      (node (ref "U$2") (pin "P$22") (pinfunction "P$22_P$22") (pintype "passive"))
      (node (ref "X1") (pin "42") (pinfunction "1_42") (pintype "passive"))
    )
    (net (code "93") (name "Net-(X1AL-1)") (class "Default")
      (node (ref "U$2") (pin "P$23") (pinfunction "P$23_P$23") (pintype "passive"))
      (node (ref "X1") (pin "43") (pinfunction "1_43") (pintype "passive"))
    )
    (net (code "94") (name "Net-(X1AM-1)") (class "Default")
      (node (ref "U$2") (pin "P$24") (pinfunction "P$24_P$24") (pintype "passive"))
      (node (ref "X1") (pin "44") (pinfunction "1_44") (pintype "passive"))
    )
    (net (code "95") (name "Net-(X1AN-1)") (class "Default")
      (node (ref "U$2") (pin "P$25") (pinfunction "P$25_P$25") (pintype "passive"))
      (node (ref "X1") (pin "45") (pinfunction "1_45") (pintype "passive"))
    )
    (net (code "96") (name "Net-(X1AO-1)") (class "Default")
      (node (ref "U$2") (pin "P$26") (pinfunction "P$26_P$26") (pintype "passive"))
      (node (ref "X1") (pin "46") (pinfunction "1_46") (pintype "passive"))
    )
    (net (code "97") (name "Net-(X1AP-1)") (class "Default")
      (node (ref "U$2") (pin "P$27") (pinfunction "P$27_P$27") (pintype "passive"))
      (node (ref "X1") (pin "47") (pinfunction "1_47") (pintype "passive"))
    )
    (net (code "98") (name "Net-(X1AQ-1)") (class "Default")
      (node (ref "U$2") (pin "P$28") (pinfunction "P$28_P$28") (pintype "passive"))
      (node (ref "X1") (pin "48") (pinfunction "1_48") (pintype "passive"))
    )
    (net (code "99") (name "Net-(X1AR-1)") (class "Default")
      (node (ref "U$2") (pin "P$29") (pinfunction "P$29_P$29") (pintype "passive"))
      (node (ref "X1") (pin "49") (pinfunction "1_49") (pintype "passive"))
    )
    (net (code "100") (name "Net-(X1AT-1)") (class "Default")
      (node (ref "U$2") (pin "P$30") (pinfunction "P$30_P$30") (pintype "passive"))
      (node (ref "X1") (pin "50") (pinfunction "1_50") (pintype "passive"))
    )
    (net (code "101") (name "Net-(X1C-1)") (class "Default")
      (node (ref "U$2") (pin "P$31") (pinfunction "P$31_P$31") (pintype "passive"))
      (node (ref "X1") (pin "11") (pinfunction "1_11") (pintype "passive"))
    )
    (net (code "102") (name "Net-(X1D-1)") (class "Default")
      (node (ref "U$2") (pin "P$32") (pinfunction "P$32_P$32") (pintype "passive"))
      (node (ref "X1") (pin "12") (pinfunction "1_12") (pintype "passive"))
    )
    (net (code "103") (name "Net-(X1E-1)") (class "Default")
      (node (ref "U$2") (pin "P$33") (pinfunction "P$33_P$33") (pintype "passive"))
      (node (ref "X1") (pin "13") (pinfunction "1_13") (pintype "passive"))
    )
    (net (code "104") (name "Net-(X1F-1)") (class "Default")
      (node (ref "U$2") (pin "P$34") (pinfunction "P$34_P$34") (pintype "passive"))
      (node (ref "X1") (pin "14") (pinfunction "1_14") (pintype "passive"))
    )
    (net (code "105") (name "Net-(X1G-1)") (class "Default")
      (node (ref "U$2") (pin "P$35") (pinfunction "P$35_P$35") (pintype "passive"))
      (node (ref "X1") (pin "15") (pinfunction "1_15") (pintype "passive"))
    )
    (net (code "106") (name "Net-(X1H-1)") (class "Default")
      (node (ref "U$2") (pin "P$36") (pinfunction "P$36_P$36") (pintype "passive"))
      (node (ref "X1") (pin "16") (pinfunction "1_16") (pintype "passive"))
    )
    (net (code "107") (name "Net-(X1I-1)") (class "Default")
      (node (ref "U$2") (pin "P$37") (pinfunction "P$37_P$37") (pintype "passive"))
      (node (ref "X1") (pin "17") (pinfunction "1_17") (pintype "passive"))
    )
    (net (code "108") (name "Net-(X1J-1)") (class "Default")
      (node (ref "U$2") (pin "P$38") (pinfunction "P$38_P$38") (pintype "passive"))
      (node (ref "X1") (pin "18") (pinfunction "1_18") (pintype "passive"))
    )
    (net (code "109") (name "Net-(X1K-1)") (class "Default")
      (node (ref "U$2") (pin "P$39") (pinfunction "P$39_P$39") (pintype "passive"))
      (node (ref "X1") (pin "19") (pinfunction "1_19") (pintype "passive"))
    )
    (net (code "110") (name "Net-(X1M-1)") (class "Default")
      (node (ref "U$2") (pin "P$40") (pinfunction "P$40_P$40") (pintype "passive"))
      (node (ref "X1") (pin "20") (pinfunction "1_20") (pintype "passive"))
    )
    (net (code "111") (name "Net-(X1N-1)") (class "Default")
      (node (ref "U$2") (pin "P$1") (pinfunction "P$1_P$1") (pintype "passive"))
      (node (ref "X1") (pin "21") (pinfunction "1_21") (pintype "passive"))
    )
    (net (code "112") (name "Net-(X1O-1)") (class "Default")
      (node (ref "U$2") (pin "P$2") (pinfunction "P$2_P$2") (pintype "passive"))
      (node (ref "X1") (pin "22") (pinfunction "1_22") (pintype "passive"))
    )
    (net (code "113") (name "Net-(X1P-1)") (class "Default")
      (node (ref "U$2") (pin "P$3") (pinfunction "P$3_P$3") (pintype "passive"))
      (node (ref "X1") (pin "23") (pinfunction "1_23") (pintype "passive"))
    )
    (net (code "114") (name "Net-(X1Q-1)") (class "Default")
      (node (ref "U$2") (pin "P$4") (pinfunction "P$4_P$4") (pintype "passive"))
      (node (ref "X1") (pin "24") (pinfunction "1_24") (pintype "passive"))
    )
    (net (code "115") (name "Net-(X1R-1)") (class "Default")
      (node (ref "U$2") (pin "P$5") (pinfunction "P$5_P$5") (pintype "passive"))
      (node (ref "X1") (pin "25") (pinfunction "1_25") (pintype "passive"))
    )
    (net (code "116") (name "Net-(X1S-1)") (class "Default")
      (node (ref "U$2") (pin "P$6") (pinfunction "P$6_P$6") (pintype "passive"))
      (node (ref "X1") (pin "26") (pinfunction "1_26") (pintype "passive"))
    )
    (net (code "117") (name "Net-(X1T-1)") (class "Default")
      (node (ref "U$2") (pin "P$7") (pinfunction "P$7_P$7") (pintype "passive"))
      (node (ref "X1") (pin "27") (pinfunction "1_27") (pintype "passive"))
    )
    (net (code "118") (name "Net-(X1U-1)") (class "Default")
      (node (ref "U$2") (pin "P$8") (pinfunction "P$8_P$8") (pintype "passive"))
      (node (ref "X1") (pin "28") (pinfunction "1_28") (pintype "passive"))
    )
    (net (code "119") (name "Net-(X1V-1)") (class "Default")
      (node (ref "U$2") (pin "P$9") (pinfunction "P$9_P$9") (pintype "passive"))
      (node (ref "X1") (pin "29") (pinfunction "1_29") (pintype "passive"))
    )
    (net (code "120") (name "Net-(X1X-1)") (class "Default")
      (node (ref "U$2") (pin "P$10") (pinfunction "P$10_P$10") (pintype "passive"))
      (node (ref "X1") (pin "30") (pinfunction "1_30") (pintype "passive"))
    )
    (net (code "121") (name "Net-(X1Y-1)") (class "Default")
      (node (ref "U$2") (pin "P$11") (pinfunction "P$11_P$11") (pintype "passive"))
      (node (ref "X1") (pin "31") (pinfunction "1_31") (pintype "passive"))
    )
    (net (code "122") (name "Net-(X1Z-1)") (class "Default")
      (node (ref "U$2") (pin "P$12") (pinfunction "P$12_P$12") (pintype "passive"))
      (node (ref "X1") (pin "32") (pinfunction "1_32") (pintype "passive"))
    )
    (net (code "123") (name "Net-(X2AA-1)") (class "Default")
      (node (ref "U$1") (pin "P$38") (pinfunction "P$38_P$38") (pintype "passive"))
      (node (ref "X2") (pin "33") (pinfunction "1_33") (pintype "passive"))
    )
    (net (code "124") (name "Net-(X2AB-1)") (class "Default")
      (node (ref "U$1") (pin "P$37") (pinfunction "P$37_P$37") (pintype "passive"))
      (node (ref "X2") (pin "34") (pinfunction "1_34") (pintype "passive"))
    )
    (net (code "125") (name "Net-(X2AC-1)") (class "Default")
      (node (ref "U$1") (pin "P$36") (pinfunction "P$36_P$36") (pintype "passive"))
      (node (ref "X2") (pin "35") (pinfunction "1_35") (pintype "passive"))
    )
    (net (code "126") (name "Net-(X2AD-1)") (class "Default")
      (node (ref "U$1") (pin "P$35") (pinfunction "P$35_P$35") (pintype "passive"))
      (node (ref "X2") (pin "36") (pinfunction "1_36") (pintype "passive"))
    )
    (net (code "127") (name "Net-(X2AE-1)") (class "Default")
      (node (ref "U$1") (pin "P$34") (pinfunction "P$34_P$34") (pintype "passive"))
      (node (ref "X2") (pin "37") (pinfunction "1_37") (pintype "passive"))
    )
    (net (code "128") (name "Net-(X2AF-1)") (class "Default")
      (node (ref "U$1") (pin "P$33") (pinfunction "P$33_P$33") (pintype "passive"))
      (node (ref "X2") (pin "38") (pinfunction "1_38") (pintype "passive"))
    )
    (net (code "129") (name "Net-(X2AG-1)") (class "Default")
      (node (ref "U$1") (pin "P$32") (pinfunction "P$32_P$32") (pintype "passive"))
      (node (ref "X2") (pin "39") (pinfunction "1_39") (pintype "passive"))
    )
    (net (code "130") (name "Net-(X2AH-1)") (class "Default")
      (node (ref "U$1") (pin "P$27") (pinfunction "P$27_P$27") (pintype "passive"))
      (node (ref "X2") (pin "4") (pinfunction "1_4") (pintype "passive"))
    )
    (net (code "131") (name "Net-(X2AI-1)") (class "Default")
      (node (ref "U$1") (pin "P$31") (pinfunction "P$31_P$31") (pintype "passive"))
      (node (ref "X2") (pin "40") (pinfunction "1_40") (pintype "passive"))
    )
    (net (code "132") (name "Net-(X2AS-1)") (class "Default")
      (node (ref "U$1") (pin "P$26") (pinfunction "P$26_P$26") (pintype "passive"))
      (node (ref "X2") (pin "5") (pinfunction "1_5") (pintype "passive"))
    )
    (net (code "133") (name "Net-(X2AU-1)") (class "Default")
      (node (ref "U$1") (pin "P$25") (pinfunction "P$25_P$25") (pintype "passive"))
      (node (ref "X2") (pin "6") (pinfunction "1_6") (pintype "passive"))
    )
    (net (code "134") (name "Net-(X2AV-1)") (class "Default")
      (node (ref "U$1") (pin "P$24") (pinfunction "P$24_P$24") (pintype "passive"))
      (node (ref "X2") (pin "7") (pinfunction "1_7") (pintype "passive"))
    )
    (net (code "135") (name "Net-(X2AW-1)") (class "Default")
      (node (ref "U$1") (pin "P$23") (pinfunction "P$23_P$23") (pintype "passive"))
      (node (ref "X2") (pin "8") (pinfunction "1_8") (pintype "passive"))
    )
    (net (code "136") (name "Net-(X2AX-1)") (class "Default")
      (node (ref "U$1") (pin "P$22") (pinfunction "P$22_P$22") (pintype "passive"))
      (node (ref "X2") (pin "9") (pinfunction "1_9") (pintype "passive"))
    )
    (net (code "137") (name "Net-(X2B-1)") (class "Default")
      (node (ref "U$1") (pin "P$21") (pinfunction "P$21_P$21") (pintype "passive"))
      (node (ref "X2") (pin "10") (pinfunction "1_10") (pintype "passive"))
    )
    (net (code "138") (name "Net-(X2C-1)") (class "Default")
      (node (ref "U$1") (pin "P$20") (pinfunction "P$20_P$20") (pintype "passive"))
      (node (ref "X2") (pin "11") (pinfunction "1_11") (pintype "passive"))
    )
    (net (code "139") (name "Net-(X2D-1)") (class "Default")
      (node (ref "U$1") (pin "P$19") (pinfunction "P$19_P$19") (pintype "passive"))
      (node (ref "X2") (pin "12") (pinfunction "1_12") (pintype "passive"))
    )
    (net (code "140") (name "Net-(X2E-1)") (class "Default")
      (node (ref "U$1") (pin "P$18") (pinfunction "P$18_P$18") (pintype "passive"))
      (node (ref "X2") (pin "13") (pinfunction "1_13") (pintype "passive"))
    )
    (net (code "141") (name "Net-(X2F-1)") (class "Default")
      (node (ref "U$1") (pin "P$17") (pinfunction "P$17_P$17") (pintype "passive"))
      (node (ref "X2") (pin "14") (pinfunction "1_14") (pintype "passive"))
    )
    (net (code "142") (name "Net-(X2G-1)") (class "Default")
      (node (ref "U$1") (pin "P$16") (pinfunction "P$16_P$16") (pintype "passive"))
      (node (ref "X2") (pin "15") (pinfunction "1_15") (pintype "passive"))
    )
    (net (code "143") (name "Net-(X2H-1)") (class "Default")
      (node (ref "U$1") (pin "P$15") (pinfunction "P$15_P$15") (pintype "passive"))
      (node (ref "X2") (pin "16") (pinfunction "1_16") (pintype "passive"))
    )
    (net (code "144") (name "Net-(X2I-1)") (class "Default")
      (node (ref "U$1") (pin "P$14") (pinfunction "P$14_P$14") (pintype "passive"))
      (node (ref "X2") (pin "17") (pinfunction "1_17") (pintype "passive"))
    )
    (net (code "145") (name "Net-(X2J-1)") (class "Default")
      (node (ref "U$1") (pin "P$13") (pinfunction "P$13_P$13") (pintype "passive"))
      (node (ref "X2") (pin "18") (pinfunction "1_18") (pintype "passive"))
    )
    (net (code "146") (name "Net-(X2K-1)") (class "Default")
      (node (ref "U$1") (pin "P$12") (pinfunction "P$12_P$12") (pintype "passive"))
      (node (ref "X2") (pin "19") (pinfunction "1_19") (pintype "passive"))
    )
    (net (code "147") (name "Net-(X2L-1)") (class "Default")
      (node (ref "U$1") (pin "P$29") (pinfunction "P$29_P$29") (pintype "passive"))
      (node (ref "X2") (pin "2") (pinfunction "1_2") (pintype "passive"))
    )
    (net (code "148") (name "Net-(X2M-1)") (class "Default")
      (node (ref "U$1") (pin "P$11") (pinfunction "P$11_P$11") (pintype "passive"))
      (node (ref "X2") (pin "20") (pinfunction "1_20") (pintype "passive"))
    )
    (net (code "149") (name "Net-(X2N-1)") (class "Default")
      (node (ref "U$1") (pin "P$10") (pinfunction "P$10_P$10") (pintype "passive"))
      (node (ref "X2") (pin "21") (pinfunction "1_21") (pintype "passive"))
    )
    (net (code "150") (name "Net-(X2O-1)") (class "Default")
      (node (ref "U$1") (pin "P$9") (pinfunction "P$9_P$9") (pintype "passive"))
      (node (ref "X2") (pin "22") (pinfunction "1_22") (pintype "passive"))
    )
    (net (code "151") (name "Net-(X2P-1)") (class "Default")
      (node (ref "U$1") (pin "P$8") (pinfunction "P$8_P$8") (pintype "passive"))
      (node (ref "X2") (pin "23") (pinfunction "1_23") (pintype "passive"))
    )
    (net (code "152") (name "Net-(X2Q-1)") (class "Default")
      (node (ref "U$1") (pin "P$7") (pinfunction "P$7_P$7") (pintype "passive"))
      (node (ref "X2") (pin "24") (pinfunction "1_24") (pintype "passive"))
    )
    (net (code "153") (name "Net-(X2R-1)") (class "Default")
      (node (ref "U$1") (pin "P$6") (pinfunction "P$6_P$6") (pintype "passive"))
      (node (ref "X2") (pin "25") (pinfunction "1_25") (pintype "passive"))
    )
    (net (code "154") (name "Net-(X2S-1)") (class "Default")
      (node (ref "U$1") (pin "P$5") (pinfunction "P$5_P$5") (pintype "passive"))
      (node (ref "X2") (pin "26") (pinfunction "1_26") (pintype "passive"))
    )
    (net (code "155") (name "Net-(X2T-1)") (class "Default")
      (node (ref "U$1") (pin "P$4") (pinfunction "P$4_P$4") (pintype "passive"))
      (node (ref "X2") (pin "27") (pinfunction "1_27") (pintype "passive"))
    )
    (net (code "156") (name "Net-(X2U-1)") (class "Default")
      (node (ref "U$1") (pin "P$3") (pinfunction "P$3_P$3") (pintype "passive"))
      (node (ref "X2") (pin "28") (pinfunction "1_28") (pintype "passive"))
    )
    (net (code "157") (name "Net-(X2V-1)") (class "Default")
      (node (ref "U$1") (pin "P$2") (pinfunction "P$2_P$2") (pintype "passive"))
      (node (ref "X2") (pin "29") (pinfunction "1_29") (pintype "passive"))
    )
    (net (code "158") (name "Net-(X2W-1)") (class "Default")
      (node (ref "U$1") (pin "P$28") (pinfunction "P$28_P$28") (pintype "passive"))
      (node (ref "X2") (pin "3") (pinfunction "1_3") (pintype "passive"))
    )
    (net (code "159") (name "Net-(X2X-1)") (class "Default")
      (node (ref "U$1") (pin "P$1") (pinfunction "P$1_P$1") (pintype "passive"))
      (node (ref "X2") (pin "30") (pinfunction "1_30") (pintype "passive"))
    )
    (net (code "160") (name "Net-(X2Y-1)") (class "Default")
      (node (ref "U$1") (pin "P$40") (pinfunction "P$40_P$40") (pintype "passive"))
      (node (ref "X2") (pin "31") (pinfunction "1_31") (pintype "passive"))
    )
    (net (code "161") (name "Net-(X2Z-1)") (class "Default")
      (node (ref "U$1") (pin "P$39") (pinfunction "P$39_P$39") (pintype "passive"))
      (node (ref "X2") (pin "32") (pinfunction "1_32") (pintype "passive"))
    )
    (net (code "162") (name "Net-(X3AA-1)") (class "Default")
      (node (ref "U$3") (pin "P$28") (pinfunction "P$28_P$28") (pintype "passive"))
      (node (ref "X3") (pin "33") (pinfunction "1_33") (pintype "passive"))
    )
    (net (code "163") (name "Net-(X3AB-1)") (class "Default")
      (node (ref "U$3") (pin "P$27") (pinfunction "P$27_P$27") (pintype "passive"))
      (node (ref "X3") (pin "34") (pinfunction "1_34") (pintype "passive"))
    )
    (net (code "164") (name "Net-(X3AC-1)") (class "Default")
      (node (ref "U$3") (pin "P$26") (pinfunction "P$26_P$26") (pintype "passive"))
      (node (ref "X3") (pin "35") (pinfunction "1_35") (pintype "passive"))
    )
    (net (code "165") (name "Net-(X3AD-1)") (class "Default")
      (node (ref "U$3") (pin "P$25") (pinfunction "P$25_P$25") (pintype "passive"))
      (node (ref "X3") (pin "36") (pinfunction "1_36") (pintype "passive"))
    )
    (net (code "166") (name "Net-(X3AE-1)") (class "Default")
      (node (ref "U$3") (pin "P$24") (pinfunction "P$24_P$24") (pintype "passive"))
      (node (ref "X3") (pin "37") (pinfunction "1_37") (pintype "passive"))
    )
    (net (code "167") (name "Net-(X3AF-1)") (class "Default")
      (node (ref "U$3") (pin "P$23") (pinfunction "P$23_P$23") (pintype "passive"))
      (node (ref "X3") (pin "38") (pinfunction "1_38") (pintype "passive"))
    )
    (net (code "168") (name "Net-(X3AG-1)") (class "Default")
      (node (ref "U$3") (pin "P$22") (pinfunction "P$22_P$22") (pintype "passive"))
      (node (ref "X3") (pin "39") (pinfunction "1_39") (pintype "passive"))
    )
    (net (code "169") (name "Net-(X3AI-1)") (class "Default")
      (node (ref "U$3") (pin "P$21") (pinfunction "P$21_P$21") (pintype "passive"))
      (node (ref "X3") (pin "40") (pinfunction "1_40") (pintype "passive"))
    )
    (net (code "170") (name "Net-(X3AJ-1)") (class "Default")
      (node (ref "U$3") (pin "P$20") (pinfunction "P$20_P$20") (pintype "passive"))
      (node (ref "X3") (pin "41") (pinfunction "1_41") (pintype "passive"))
    )
    (net (code "171") (name "Net-(X3AK-1)") (class "Default")
      (node (ref "U$3") (pin "P$19") (pinfunction "P$19_P$19") (pintype "passive"))
      (node (ref "X3") (pin "42") (pinfunction "1_42") (pintype "passive"))
    )
    (net (code "172") (name "Net-(X3AL-1)") (class "Default")
      (node (ref "U$3") (pin "P$18") (pinfunction "P$18_P$18") (pintype "passive"))
      (node (ref "X3") (pin "43") (pinfunction "1_43") (pintype "passive"))
    )
    (net (code "173") (name "Net-(X3AM-1)") (class "Default")
      (node (ref "U$3") (pin "P$17") (pinfunction "P$17_P$17") (pintype "passive"))
      (node (ref "X3") (pin "44") (pinfunction "1_44") (pintype "passive"))
    )
    (net (code "174") (name "Net-(X3AN-1)") (class "Default")
      (node (ref "U$3") (pin "P$16") (pinfunction "P$16_P$16") (pintype "passive"))
      (node (ref "X3") (pin "45") (pinfunction "1_45") (pintype "passive"))
    )
    (net (code "175") (name "Net-(X3AO-1)") (class "Default")
      (node (ref "U$3") (pin "P$15") (pinfunction "P$15_P$15") (pintype "passive"))
      (node (ref "X3") (pin "46") (pinfunction "1_46") (pintype "passive"))
    )
    (net (code "176") (name "Net-(X3AP-1)") (class "Default")
      (node (ref "U$3") (pin "P$14") (pinfunction "P$14_P$14") (pintype "passive"))
      (node (ref "X3") (pin "47") (pinfunction "1_47") (pintype "passive"))
    )
    (net (code "177") (name "Net-(X3AQ-1)") (class "Default")
      (node (ref "U$3") (pin "P$13") (pinfunction "P$13_P$13") (pintype "passive"))
      (node (ref "X3") (pin "48") (pinfunction "1_48") (pintype "passive"))
    )
    (net (code "178") (name "Net-(X3AR-1)") (class "Default")
      (node (ref "U$3") (pin "P$12") (pinfunction "P$12_P$12") (pintype "passive"))
      (node (ref "X3") (pin "49") (pinfunction "1_49") (pintype "passive"))
    )
    (net (code "179") (name "Net-(X3AT-1)") (class "Default")
      (node (ref "U$3") (pin "P$11") (pinfunction "P$11_P$11") (pintype "passive"))
      (node (ref "X3") (pin "50") (pinfunction "1_50") (pintype "passive"))
    )
    (net (code "180") (name "Net-(X3C-1)") (class "Default")
      (node (ref "U$3") (pin "P$10") (pinfunction "P$10_P$10") (pintype "passive"))
      (node (ref "X3") (pin "11") (pinfunction "1_11") (pintype "passive"))
    )
    (net (code "181") (name "Net-(X3D-1)") (class "Default")
      (node (ref "U$3") (pin "P$9") (pinfunction "P$9_P$9") (pintype "passive"))
      (node (ref "X3") (pin "12") (pinfunction "1_12") (pintype "passive"))
    )
    (net (code "182") (name "Net-(X3E-1)") (class "Default")
      (node (ref "U$3") (pin "P$8") (pinfunction "P$8_P$8") (pintype "passive"))
      (node (ref "X3") (pin "13") (pinfunction "1_13") (pintype "passive"))
    )
    (net (code "183") (name "Net-(X3F-1)") (class "Default")
      (node (ref "U$3") (pin "P$7") (pinfunction "P$7_P$7") (pintype "passive"))
      (node (ref "X3") (pin "14") (pinfunction "1_14") (pintype "passive"))
    )
    (net (code "184") (name "Net-(X3G-1)") (class "Default")
      (node (ref "U$3") (pin "P$6") (pinfunction "P$6_P$6") (pintype "passive"))
      (node (ref "X3") (pin "15") (pinfunction "1_15") (pintype "passive"))
    )
    (net (code "185") (name "Net-(X3H-1)") (class "Default")
      (node (ref "U$3") (pin "P$5") (pinfunction "P$5_P$5") (pintype "passive"))
      (node (ref "X3") (pin "16") (pinfunction "1_16") (pintype "passive"))
    )
    (net (code "186") (name "Net-(X3I-1)") (class "Default")
      (node (ref "U$3") (pin "P$4") (pinfunction "P$4_P$4") (pintype "passive"))
      (node (ref "X3") (pin "17") (pinfunction "1_17") (pintype "passive"))
    )
    (net (code "187") (name "Net-(X3J-1)") (class "Default")
      (node (ref "U$3") (pin "P$3") (pinfunction "P$3_P$3") (pintype "passive"))
      (node (ref "X3") (pin "18") (pinfunction "1_18") (pintype "passive"))
    )
    (net (code "188") (name "Net-(X3K-1)") (class "Default")
      (node (ref "U$3") (pin "P$2") (pinfunction "P$2_P$2") (pintype "passive"))
      (node (ref "X3") (pin "19") (pinfunction "1_19") (pintype "passive"))
    )
    (net (code "189") (name "Net-(X3M-1)") (class "Default")
      (node (ref "U$3") (pin "P$1") (pinfunction "P$1_P$1") (pintype "passive"))
      (node (ref "X3") (pin "20") (pinfunction "1_20") (pintype "passive"))
    )
    (net (code "190") (name "Net-(X3N-1)") (class "Default")
      (node (ref "U$3") (pin "P$40") (pinfunction "P$40_P$40") (pintype "passive"))
      (node (ref "X3") (pin "21") (pinfunction "1_21") (pintype "passive"))
    )
    (net (code "191") (name "Net-(X3O-1)") (class "Default")
      (node (ref "U$3") (pin "P$39") (pinfunction "P$39_P$39") (pintype "passive"))
      (node (ref "X3") (pin "22") (pinfunction "1_22") (pintype "passive"))
    )
    (net (code "192") (name "Net-(X3P-1)") (class "Default")
      (node (ref "U$3") (pin "P$38") (pinfunction "P$38_P$38") (pintype "passive"))
      (node (ref "X3") (pin "23") (pinfunction "1_23") (pintype "passive"))
    )
    (net (code "193") (name "Net-(X3Q-1)") (class "Default")
      (node (ref "U$3") (pin "P$37") (pinfunction "P$37_P$37") (pintype "passive"))
      (node (ref "X3") (pin "24") (pinfunction "1_24") (pintype "passive"))
    )
    (net (code "194") (name "Net-(X3R-1)") (class "Default")
      (node (ref "U$3") (pin "P$36") (pinfunction "P$36_P$36") (pintype "passive"))
      (node (ref "X3") (pin "25") (pinfunction "1_25") (pintype "passive"))
    )
    (net (code "195") (name "Net-(X3S-1)") (class "Default")
      (node (ref "U$3") (pin "P$35") (pinfunction "P$35_P$35") (pintype "passive"))
      (node (ref "X3") (pin "26") (pinfunction "1_26") (pintype "passive"))
    )
    (net (code "196") (name "Net-(X3T-1)") (class "Default")
      (node (ref "U$3") (pin "P$34") (pinfunction "P$34_P$34") (pintype "passive"))
      (node (ref "X3") (pin "27") (pinfunction "1_27") (pintype "passive"))
    )
    (net (code "197") (name "Net-(X3U-1)") (class "Default")
      (node (ref "U$3") (pin "P$33") (pinfunction "P$33_P$33") (pintype "passive"))
      (node (ref "X3") (pin "28") (pinfunction "1_28") (pintype "passive"))
    )
    (net (code "198") (name "Net-(X3V-1)") (class "Default")
      (node (ref "U$3") (pin "P$32") (pinfunction "P$32_P$32") (pintype "passive"))
      (node (ref "X3") (pin "29") (pinfunction "1_29") (pintype "passive"))
    )
    (net (code "199") (name "Net-(X3X-1)") (class "Default")
      (node (ref "U$3") (pin "P$31") (pinfunction "P$31_P$31") (pintype "passive"))
      (node (ref "X3") (pin "30") (pinfunction "1_30") (pintype "passive"))
    )
    (net (code "200") (name "Net-(X3Y-1)") (class "Default")
      (node (ref "U$3") (pin "P$30") (pinfunction "P$30_P$30") (pintype "passive"))
      (node (ref "X3") (pin "31") (pinfunction "1_31") (pintype "passive"))
    )
    (net (code "201") (name "Net-(X3Z-1)") (class "Default")
      (node (ref "U$3") (pin "P$29") (pinfunction "P$29_P$29") (pintype "passive"))
      (node (ref "X3") (pin "32") (pinfunction "1_32") (pintype "passive"))
    )
    (net (code "202") (name "Net-(X5AA-1)") (class "Default")
      (node (ref "U$40PIN-BACK") (pin "P$3") (pinfunction "P$3_P$3") (pintype "passive"))
      (node (ref "X5") (pin "33") (pinfunction "1_33") (pintype "passive"))
    )
    (net (code "203") (name "Net-(X5AB-1)") (class "Default")
      (node (ref "U$40PIN-BACK") (pin "P$4") (pinfunction "P$4_P$4") (pintype "passive"))
      (node (ref "X5") (pin "34") (pinfunction "1_34") (pintype "passive"))
    )
    (net (code "204") (name "Net-(X5AC-1)") (class "Default")
      (node (ref "U$40PIN-BACK") (pin "P$5") (pinfunction "P$5_P$5") (pintype "passive"))
      (node (ref "X5") (pin "35") (pinfunction "1_35") (pintype "passive"))
    )
    (net (code "205") (name "Net-(X5AD-1)") (class "Default")
      (node (ref "U$40PIN-BACK") (pin "P$6") (pinfunction "P$6_P$6") (pintype "passive"))
      (node (ref "X5") (pin "36") (pinfunction "1_36") (pintype "passive"))
    )
    (net (code "206") (name "Net-(X5AE-1)") (class "Default")
      (node (ref "U$40PIN-BACK") (pin "P$7") (pinfunction "P$7_P$7") (pintype "passive"))
      (node (ref "X5") (pin "37") (pinfunction "1_37") (pintype "passive"))
    )
    (net (code "207") (name "Net-(X5AF-1)") (class "Default")
      (node (ref "U$40PIN-BACK") (pin "P$8") (pinfunction "P$8_P$8") (pintype "passive"))
      (node (ref "X5") (pin "38") (pinfunction "1_38") (pintype "passive"))
    )
    (net (code "208") (name "Net-(X5AG-1)") (class "Default")
      (node (ref "U$40PIN-BACK") (pin "P$9") (pinfunction "P$9_P$9") (pintype "passive"))
      (node (ref "X5") (pin "39") (pinfunction "1_39") (pintype "passive"))
    )
    (net (code "209") (name "Net-(X5AH-1)") (class "Default")
      (node (ref "U$40PIN-BACK") (pin "P$14") (pinfunction "P$14_P$14") (pintype "passive"))
      (node (ref "X5") (pin "4") (pinfunction "1_4") (pintype "passive"))
    )
    (net (code "210") (name "Net-(X5AI-1)") (class "Default")
      (node (ref "U$40PIN-BACK") (pin "P$10") (pinfunction "P$10_P$10") (pintype "passive"))
      (node (ref "X5") (pin "40") (pinfunction "1_40") (pintype "passive"))
    )
    (net (code "211") (name "Net-(X5AS-1)") (class "Default")
      (node (ref "U$40PIN-BACK") (pin "P$15") (pinfunction "P$15_P$15") (pintype "passive"))
      (node (ref "X5") (pin "5") (pinfunction "1_5") (pintype "passive"))
    )
    (net (code "212") (name "Net-(X5AU-1)") (class "Default")
      (node (ref "U$40PIN-BACK") (pin "P$16") (pinfunction "P$16_P$16") (pintype "passive"))
      (node (ref "X5") (pin "6") (pinfunction "1_6") (pintype "passive"))
    )
    (net (code "213") (name "Net-(X5AV-1)") (class "Default")
      (node (ref "U$40PIN-BACK") (pin "P$17") (pinfunction "P$17_P$17") (pintype "passive"))
      (node (ref "X5") (pin "7") (pinfunction "1_7") (pintype "passive"))
    )
    (net (code "214") (name "Net-(X5AW-1)") (class "Default")
      (node (ref "U$40PIN-BACK") (pin "P$18") (pinfunction "P$18_P$18") (pintype "passive"))
      (node (ref "X5") (pin "8") (pinfunction "1_8") (pintype "passive"))
    )
    (net (code "215") (name "Net-(X5AX-1)") (class "Default")
      (node (ref "U$40PIN-BACK") (pin "P$19") (pinfunction "P$19_P$19") (pintype "passive"))
      (node (ref "X5") (pin "9") (pinfunction "1_9") (pintype "passive"))
    )
    (net (code "216") (name "Net-(X5B-1)") (class "Default")
      (node (ref "U$40PIN-BACK") (pin "P$20") (pinfunction "P$20_P$20") (pintype "passive"))
      (node (ref "X5") (pin "10") (pinfunction "1_10") (pintype "passive"))
    )
    (net (code "217") (name "Net-(X5C-1)") (class "Default")
      (node (ref "U$40PIN-BACK") (pin "P$21") (pinfunction "P$21_P$21") (pintype "passive"))
      (node (ref "X5") (pin "11") (pinfunction "1_11") (pintype "passive"))
    )
    (net (code "218") (name "Net-(X5D-1)") (class "Default")
      (node (ref "U$40PIN-BACK") (pin "P$22") (pinfunction "P$22_P$22") (pintype "passive"))
      (node (ref "X5") (pin "12") (pinfunction "1_12") (pintype "passive"))
    )
    (net (code "219") (name "Net-(X5E-1)") (class "Default")
      (node (ref "U$40PIN-BACK") (pin "P$23") (pinfunction "P$23_P$23") (pintype "passive"))
      (node (ref "X5") (pin "13") (pinfunction "1_13") (pintype "passive"))
    )
    (net (code "220") (name "Net-(X5F-1)") (class "Default")
      (node (ref "U$40PIN-BACK") (pin "P$24") (pinfunction "P$24_P$24") (pintype "passive"))
      (node (ref "X5") (pin "14") (pinfunction "1_14") (pintype "passive"))
    )
    (net (code "221") (name "Net-(X5G-1)") (class "Default")
      (node (ref "U$40PIN-BACK") (pin "P$25") (pinfunction "P$25_P$25") (pintype "passive"))
      (node (ref "X5") (pin "15") (pinfunction "1_15") (pintype "passive"))
    )
    (net (code "222") (name "Net-(X5H-1)") (class "Default")
      (node (ref "U$40PIN-BACK") (pin "P$26") (pinfunction "P$26_P$26") (pintype "passive"))
      (node (ref "X5") (pin "16") (pinfunction "1_16") (pintype "passive"))
    )
    (net (code "223") (name "Net-(X5I-1)") (class "Default")
      (node (ref "U$40PIN-BACK") (pin "P$27") (pinfunction "P$27_P$27") (pintype "passive"))
      (node (ref "X5") (pin "17") (pinfunction "1_17") (pintype "passive"))
    )
    (net (code "224") (name "Net-(X5J-1)") (class "Default")
      (node (ref "U$40PIN-BACK") (pin "P$28") (pinfunction "P$28_P$28") (pintype "passive"))
      (node (ref "X5") (pin "18") (pinfunction "1_18") (pintype "passive"))
    )
    (net (code "225") (name "Net-(X5K-1)") (class "Default")
      (node (ref "U$40PIN-BACK") (pin "P$29") (pinfunction "P$29_P$29") (pintype "passive"))
      (node (ref "X5") (pin "19") (pinfunction "1_19") (pintype "passive"))
    )
    (net (code "226") (name "Net-(X5L-1)") (class "Default")
      (node (ref "U$40PIN-BACK") (pin "P$12") (pinfunction "P$12_P$12") (pintype "passive"))
      (node (ref "X5") (pin "2") (pinfunction "1_2") (pintype "passive"))
    )
    (net (code "227") (name "Net-(X5M-1)") (class "Default")
      (node (ref "U$40PIN-BACK") (pin "P$30") (pinfunction "P$30_P$30") (pintype "passive"))
      (node (ref "X5") (pin "20") (pinfunction "1_20") (pintype "passive"))
    )
    (net (code "228") (name "Net-(X5N-1)") (class "Default")
      (node (ref "U$40PIN-BACK") (pin "P$31") (pinfunction "P$31_P$31") (pintype "passive"))
      (node (ref "X5") (pin "21") (pinfunction "1_21") (pintype "passive"))
    )
    (net (code "229") (name "Net-(X5O-1)") (class "Default")
      (node (ref "U$40PIN-BACK") (pin "P$32") (pinfunction "P$32_P$32") (pintype "passive"))
      (node (ref "X5") (pin "22") (pinfunction "1_22") (pintype "passive"))
    )
    (net (code "230") (name "Net-(X5P-1)") (class "Default")
      (node (ref "U$40PIN-BACK") (pin "P$33") (pinfunction "P$33_P$33") (pintype "passive"))
      (node (ref "X5") (pin "23") (pinfunction "1_23") (pintype "passive"))
    )
    (net (code "231") (name "Net-(X5Q-1)") (class "Default")
      (node (ref "U$40PIN-BACK") (pin "P$34") (pinfunction "P$34_P$34") (pintype "passive"))
      (node (ref "X5") (pin "24") (pinfunction "1_24") (pintype "passive"))
    )
    (net (code "232") (name "Net-(X5R-1)") (class "Default")
      (node (ref "U$40PIN-BACK") (pin "P$35") (pinfunction "P$35_P$35") (pintype "passive"))
      (node (ref "X5") (pin "25") (pinfunction "1_25") (pintype "passive"))
    )
    (net (code "233") (name "Net-(X5S-1)") (class "Default")
      (node (ref "U$40PIN-BACK") (pin "P$36") (pinfunction "P$36_P$36") (pintype "passive"))
      (node (ref "X5") (pin "26") (pinfunction "1_26") (pintype "passive"))
    )
    (net (code "234") (name "Net-(X5T-1)") (class "Default")
      (node (ref "U$40PIN-BACK") (pin "P$37") (pinfunction "P$37_P$37") (pintype "passive"))
      (node (ref "X5") (pin "27") (pinfunction "1_27") (pintype "passive"))
    )
    (net (code "235") (name "Net-(X5U-1)") (class "Default")
      (node (ref "U$40PIN-BACK") (pin "P$38") (pinfunction "P$38_P$38") (pintype "passive"))
      (node (ref "X5") (pin "28") (pinfunction "1_28") (pintype "passive"))
    )
    (net (code "236") (name "Net-(X5V-1)") (class "Default")
      (node (ref "U$40PIN-BACK") (pin "P$39") (pinfunction "P$39_P$39") (pintype "passive"))
      (node (ref "X5") (pin "29") (pinfunction "1_29") (pintype "passive"))
    )
    (net (code "237") (name "Net-(X5W-1)") (class "Default")
      (node (ref "U$40PIN-BACK") (pin "P$13") (pinfunction "P$13_P$13") (pintype "passive"))
      (node (ref "X5") (pin "3") (pinfunction "1_3") (pintype "passive"))
    )
    (net (code "238") (name "Net-(X5X-1)") (class "Default")
      (node (ref "U$40PIN-BACK") (pin "P$40") (pinfunction "P$40_P$40") (pintype "passive"))
      (node (ref "X5") (pin "30") (pinfunction "1_30") (pintype "passive"))
    )
    (net (code "239") (name "Net-(X5Y-1)") (class "Default")
      (node (ref "U$40PIN-BACK") (pin "P$1") (pinfunction "P$1_P$1") (pintype "passive"))
      (node (ref "X5") (pin "31") (pinfunction "1_31") (pintype "passive"))
    )
    (net (code "240") (name "Net-(X5Z-1)") (class "Default")
      (node (ref "U$40PIN-BACK") (pin "P$2") (pinfunction "P$2_P$2") (pintype "passive"))
      (node (ref "X5") (pin "32") (pinfunction "1_32") (pintype "passive"))
    )
    (net (code "241") (name "unconnected-(X1AS-1-Pad5)") (class "Default")
      (node (ref "X1") (pin "5") (pinfunction "1_5") (pintype "passive"))
    )
    (net (code "242") (name "unconnected-(X1AU-1-Pad6)") (class "Default")
      (node (ref "X1") (pin "6") (pinfunction "1_6") (pintype "passive"))
    )
    (net (code "243") (name "unconnected-(X1AV-1-Pad7)") (class "Default")
      (node (ref "X1") (pin "7") (pinfunction "1_7") (pintype "passive"))
    )
    (net (code "244") (name "unconnected-(X1AW-1-Pad8)") (class "Default")
      (node (ref "X1") (pin "8") (pinfunction "1_8") (pintype "passive"))
    )
    (net (code "245") (name "unconnected-(X1AX-1-Pad9)") (class "Default")
      (node (ref "X1") (pin "9") (pinfunction "1_9") (pintype "passive"))
    )
    (net (code "246") (name "unconnected-(X1B-1-Pad10)") (class "Default")
      (node (ref "X1") (pin "10") (pinfunction "1_10") (pintype "passive"))
    )
    (net (code "247") (name "unconnected-(X2AJ-1-Pad41)") (class "Default")
      (node (ref "X2") (pin "41") (pinfunction "1_41") (pintype "passive"))
    )
    (net (code "248") (name "unconnected-(X2AK-1-Pad42)") (class "Default")
      (node (ref "X2") (pin "42") (pinfunction "1_42") (pintype "passive"))
    )
    (net (code "249") (name "unconnected-(X2AL-1-Pad43)") (class "Default")
      (node (ref "X2") (pin "43") (pinfunction "1_43") (pintype "passive"))
    )
    (net (code "250") (name "unconnected-(X2AM-1-Pad44)") (class "Default")
      (node (ref "X2") (pin "44") (pinfunction "1_44") (pintype "passive"))
    )
    (net (code "251") (name "unconnected-(X2AN-1-Pad45)") (class "Default")
      (node (ref "X2") (pin "45") (pinfunction "1_45") (pintype "passive"))
    )
    (net (code "252") (name "unconnected-(X2AO-1-Pad46)") (class "Default")
      (node (ref "X2") (pin "46") (pinfunction "1_46") (pintype "passive"))
    )
    (net (code "253") (name "unconnected-(X2AP-1-Pad47)") (class "Default")
      (node (ref "X2") (pin "47") (pinfunction "1_47") (pintype "passive"))
    )
    (net (code "254") (name "unconnected-(X2AQ-1-Pad48)") (class "Default")
      (node (ref "X2") (pin "48") (pinfunction "1_48") (pintype "passive"))
    )
    (net (code "255") (name "unconnected-(X2AR-1-Pad49)") (class "Default")
      (node (ref "X2") (pin "49") (pinfunction "1_49") (pintype "passive"))
    )
    (net (code "256") (name "unconnected-(X2AT-1-Pad50)") (class "Default")
      (node (ref "X2") (pin "50") (pinfunction "1_50") (pintype "passive"))
    )
    (net (code "257") (name "unconnected-(X3-Pad1)") (class "Default")
      (node (ref "X3") (pin "1") (pinfunction "1_1") (pintype "passive"))
    )
    (net (code "258") (name "unconnected-(X3AH-1-Pad4)") (class "Default")
      (node (ref "X3") (pin "4") (pinfunction "1_4") (pintype "passive"))
    )
    (net (code "259") (name "unconnected-(X3AS-1-Pad5)") (class "Default")
      (node (ref "X3") (pin "5") (pinfunction "1_5") (pintype "passive"))
    )
    (net (code "260") (name "unconnected-(X3AU-1-Pad6)") (class "Default")
      (node (ref "X3") (pin "6") (pinfunction "1_6") (pintype "passive"))
    )
    (net (code "261") (name "unconnected-(X3AV-1-Pad7)") (class "Default")
      (node (ref "X3") (pin "7") (pinfunction "1_7") (pintype "passive"))
    )
    (net (code "262") (name "unconnected-(X3AW-1-Pad8)") (class "Default")
      (node (ref "X3") (pin "8") (pinfunction "1_8") (pintype "passive"))
    )
    (net (code "263") (name "unconnected-(X3AX-1-Pad9)") (class "Default")
      (node (ref "X3") (pin "9") (pinfunction "1_9") (pintype "passive"))
    )
    (net (code "264") (name "unconnected-(X3B-1-Pad10)") (class "Default")
      (node (ref "X3") (pin "10") (pinfunction "1_10") (pintype "passive"))
    )
    (net (code "265") (name "unconnected-(X3L-1-Pad2)") (class "Default")
      (node (ref "X3") (pin "2") (pinfunction "1_2") (pintype "passive"))
    )
    (net (code "266") (name "unconnected-(X3W-1-Pad3)") (class "Default")
      (node (ref "X3") (pin "3") (pinfunction "1_3") (pintype "passive"))
    )
    (net (code "267") (name "unconnected-(X5AJ-1-Pad41)") (class "Default")
      (node (ref "X5") (pin "41") (pinfunction "1_41") (pintype "passive"))
    )
    (net (code "268") (name "unconnected-(X5AK-1-Pad42)") (class "Default")
      (node (ref "X5") (pin "42") (pinfunction "1_42") (pintype "passive"))
    )
    (net (code "269") (name "unconnected-(X5AL-1-Pad43)") (class "Default")
      (node (ref "X5") (pin "43") (pinfunction "1_43") (pintype "passive"))
    )
    (net (code "270") (name "unconnected-(X5AM-1-Pad44)") (class "Default")
      (node (ref "X5") (pin "44") (pinfunction "1_44") (pintype "passive"))
    )
    (net (code "271") (name "unconnected-(X5AN-1-Pad45)") (class "Default")
      (node (ref "X5") (pin "45") (pinfunction "1_45") (pintype "passive"))
    )
    (net (code "272") (name "unconnected-(X5AO-1-Pad46)") (class "Default")
      (node (ref "X5") (pin "46") (pinfunction "1_46") (pintype "passive"))
    )
  )
)
